# DIfferential_Current_DAC.net
KiCad netlist of a schematic drawn in Altium Designer
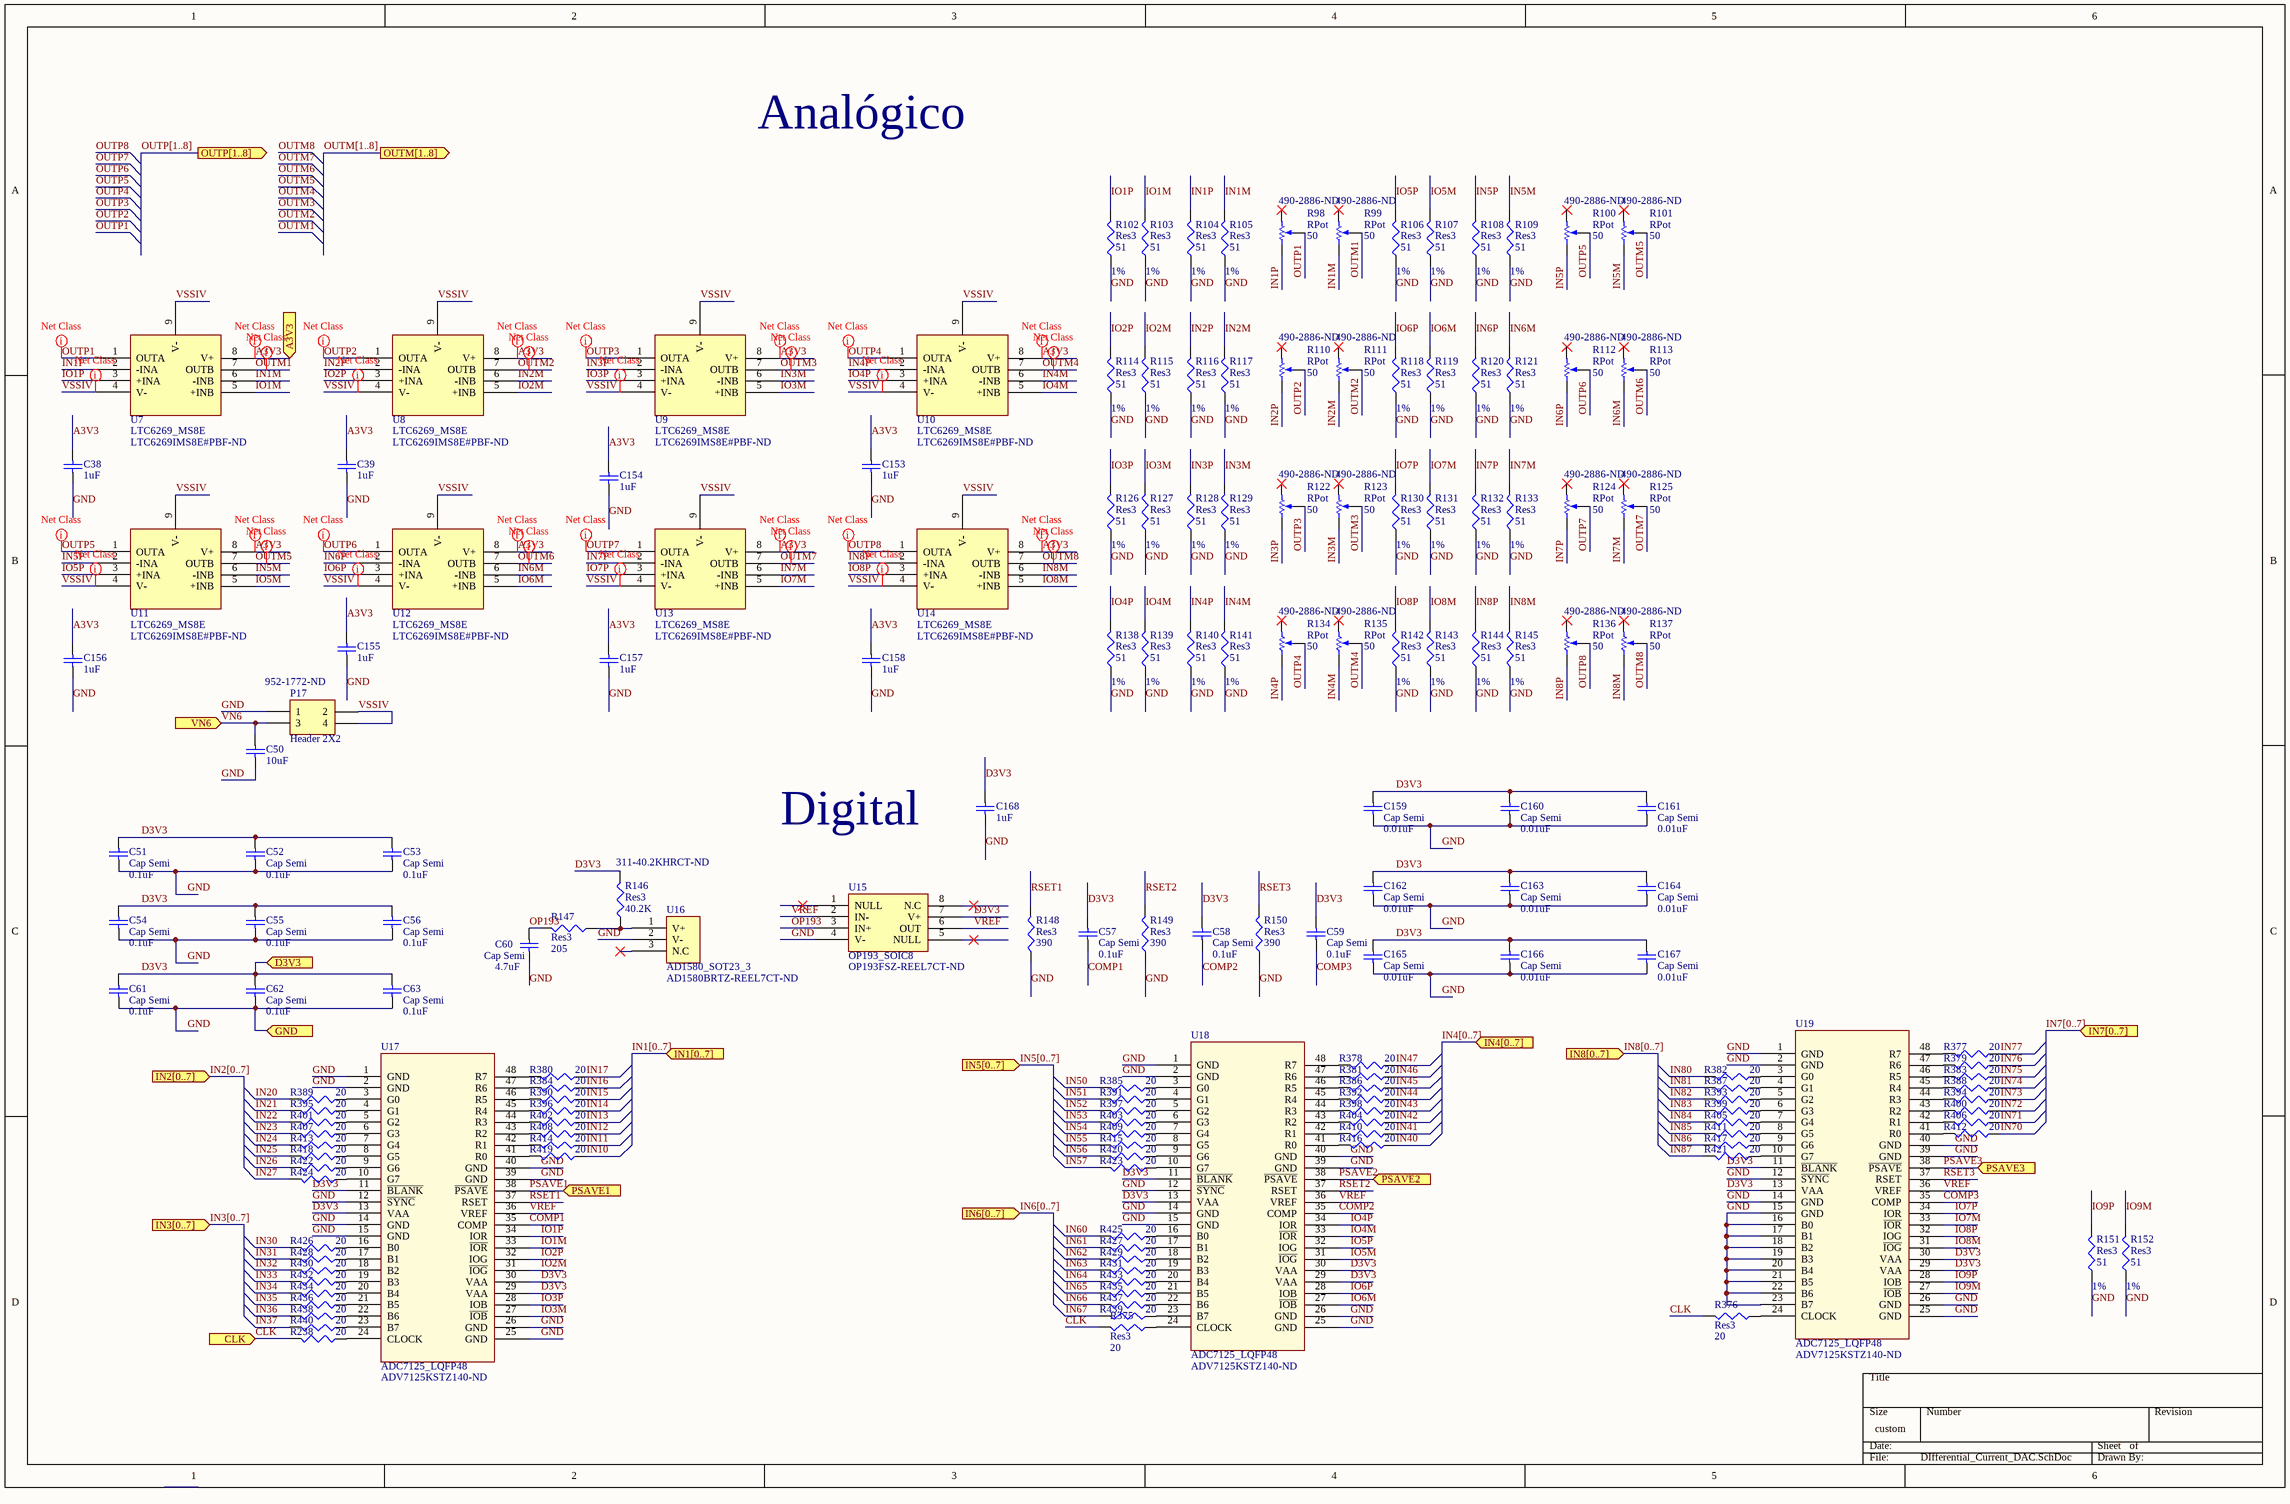
[diagram p0: DIfferential_Current_DAC.SchDoc]

(export (version "E")
  (design (tool "Eeschema 10.0.6"))
  (components
    (comp (ref "C38")
      (value "1uF")
      (footprint "J1-0603")
      (description "Capacitor")
      (fields (field (name "Comment") "Cap") (field (name "PUBLISHER") "Altium Limited"))
      (libsource (lib "Miscellaneous Devices") (part "Cap"))
    )
    (comp (ref "C39")
      (value "1uF")
      (footprint "J1-0603")
      (description "Capacitor")
      (fields (field (name "Comment") "Cap") (field (name "PUBLISHER") "Altium Limited"))
      (libsource (lib "Miscellaneous Devices") (part "Cap"))
    )
    (comp (ref "C50")
      (value "10uF")
      (footprint "RES_0805")
      (description "Capacitor")
      (fields (field (name "Comment") "Cap") (field (name "PUBLISHER") "Altium Limited"))
      (libsource (lib "Miscellaneous Devices") (part "Cap"))
    )
    (comp (ref "C51")
      (value "Cap Semi")
      (footprint "J1-0603")
      (description "Capacitor (Semiconductor SIM Model)")
      (fields (field (name "ALTIUM_VALUE") "0.1uF") (field (name "PUBLISHER") "Altium Limited"))
      (libsource (lib "Miscellaneous Devices") (part "Cap Semi"))
    )
    (comp (ref "C52")
      (value "Cap Semi")
      (footprint "J1-0603")
      (description "Capacitor (Semiconductor SIM Model)")
      (fields (field (name "ALTIUM_VALUE") "0.1uF") (field (name "PUBLISHER") "Altium Limited"))
      (libsource (lib "Miscellaneous Devices") (part "Cap Semi"))
    )
    (comp (ref "C53")
      (value "Cap Semi")
      (footprint "J1-0603")
      (description "Capacitor (Semiconductor SIM Model)")
      (fields (field (name "ALTIUM_VALUE") "0.1uF") (field (name "PUBLISHER") "Altium Limited"))
      (libsource (lib "Miscellaneous Devices") (part "Cap Semi"))
    )
    (comp (ref "C54")
      (value "Cap Semi")
      (footprint "J1-0603")
      (description "Capacitor (Semiconductor SIM Model)")
      (fields (field (name "ALTIUM_VALUE") "0.1uF") (field (name "PUBLISHER") "Altium Limited"))
      (libsource (lib "Miscellaneous Devices") (part "Cap Semi"))
    )
    (comp (ref "C55")
      (value "Cap Semi")
      (footprint "J1-0603")
      (description "Capacitor (Semiconductor SIM Model)")
      (fields (field (name "ALTIUM_VALUE") "0.1uF") (field (name "PUBLISHER") "Altium Limited"))
      (libsource (lib "Miscellaneous Devices") (part "Cap Semi"))
    )
    (comp (ref "C56")
      (value "Cap Semi")
      (footprint "J1-0603")
      (description "Capacitor (Semiconductor SIM Model)")
      (fields (field (name "ALTIUM_VALUE") "0.1uF") (field (name "PUBLISHER") "Altium Limited"))
      (libsource (lib "Miscellaneous Devices") (part "Cap Semi"))
    )
    (comp (ref "C57")
      (value "Cap Semi")
      (footprint "J1-0603")
      (description "Capacitor (Semiconductor SIM Model)")
      (fields (field (name "ALTIUM_VALUE") "0.1uF") (field (name "PUBLISHER") "Altium Limited"))
      (libsource (lib "Miscellaneous Devices") (part "Cap Semi"))
    )
    (comp (ref "C58")
      (value "Cap Semi")
      (footprint "J1-0603")
      (description "Capacitor (Semiconductor SIM Model)")
      (fields (field (name "ALTIUM_VALUE") "0.1uF") (field (name "PUBLISHER") "Altium Limited"))
      (libsource (lib "Miscellaneous Devices") (part "Cap Semi"))
    )
    (comp (ref "C59")
      (value "Cap Semi")
      (footprint "J1-0603")
      (description "Capacitor (Semiconductor SIM Model)")
      (fields (field (name "ALTIUM_VALUE") "0.1uF") (field (name "PUBLISHER") "Altium Limited"))
      (libsource (lib "Miscellaneous Devices") (part "Cap Semi"))
    )
    (comp (ref "C60")
      (value "Cap Semi")
      (footprint "J1-0603")
      (description "Capacitor (Semiconductor SIM Model)")
      (fields (field (name "ALTIUM_VALUE") "4.7uF") (field (name "PUBLISHER") "Altium Limited"))
      (libsource (lib "Miscellaneous Devices") (part "Cap Semi"))
    )
    (comp (ref "C61")
      (value "Cap Semi")
      (footprint "J1-0603")
      (description "Capacitor (Semiconductor SIM Model)")
      (fields (field (name "ALTIUM_VALUE") "0.1uF") (field (name "PUBLISHER") "Altium Limited"))
      (libsource (lib "Miscellaneous Devices") (part "Cap Semi"))
    )
    (comp (ref "C62")
      (value "Cap Semi")
      (footprint "J1-0603")
      (description "Capacitor (Semiconductor SIM Model)")
      (fields (field (name "ALTIUM_VALUE") "0.1uF") (field (name "PUBLISHER") "Altium Limited"))
      (libsource (lib "Miscellaneous Devices") (part "Cap Semi"))
    )
    (comp (ref "C63")
      (value "Cap Semi")
      (footprint "J1-0603")
      (description "Capacitor (Semiconductor SIM Model)")
      (fields (field (name "ALTIUM_VALUE") "0.1uF") (field (name "PUBLISHER") "Altium Limited"))
      (libsource (lib "Miscellaneous Devices") (part "Cap Semi"))
    )
    (comp (ref "C153")
      (value "1uF")
      (footprint "J1-0603")
      (description "Capacitor")
      (fields (field (name "Comment") "Cap") (field (name "PUBLISHER") "Altium Limited"))
      (libsource (lib "Miscellaneous Devices") (part "Cap"))
    )
    (comp (ref "C154")
      (value "1uF")
      (footprint "J1-0603")
      (description "Capacitor")
      (fields (field (name "Comment") "Cap") (field (name "PUBLISHER") "Altium Limited"))
      (libsource (lib "Miscellaneous Devices") (part "Cap"))
    )
    (comp (ref "C155")
      (value "1uF")
      (footprint "J1-0603")
      (description "Capacitor")
      (fields (field (name "Comment") "Cap") (field (name "PUBLISHER") "Altium Limited"))
      (libsource (lib "Miscellaneous Devices") (part "Cap"))
    )
    (comp (ref "C156")
      (value "1uF")
      (footprint "J1-0603")
      (description "Capacitor")
      (fields (field (name "Comment") "Cap") (field (name "PUBLISHER") "Altium Limited"))
      (libsource (lib "Miscellaneous Devices") (part "Cap"))
    )
    (comp (ref "C157")
      (value "1uF")
      (footprint "J1-0603")
      (description "Capacitor")
      (fields (field (name "Comment") "Cap") (field (name "PUBLISHER") "Altium Limited"))
      (libsource (lib "Miscellaneous Devices") (part "Cap"))
    )
    (comp (ref "C158")
      (value "1uF")
      (footprint "J1-0603")
      (description "Capacitor")
      (fields (field (name "Comment") "Cap") (field (name "PUBLISHER") "Altium Limited"))
      (libsource (lib "Miscellaneous Devices") (part "Cap"))
    )
    (comp (ref "C159")
      (value "Cap Semi")
      (footprint "J1-0603")
      (description "Capacitor (Semiconductor SIM Model)")
      (fields (field (name "ALTIUM_VALUE") "0.01uF") (field (name "PUBLISHER") "Altium Limited"))
      (libsource (lib "Miscellaneous Devices") (part "Cap Semi"))
    )
    (comp (ref "C160")
      (value "Cap Semi")
      (footprint "J1-0603")
      (description "Capacitor (Semiconductor SIM Model)")
      (fields (field (name "ALTIUM_VALUE") "0.01uF") (field (name "PUBLISHER") "Altium Limited"))
      (libsource (lib "Miscellaneous Devices") (part "Cap Semi"))
    )
    (comp (ref "C161")
      (value "Cap Semi")
      (footprint "J1-0603")
      (description "Capacitor (Semiconductor SIM Model)")
      (fields (field (name "ALTIUM_VALUE") "0.01uF") (field (name "PUBLISHER") "Altium Limited"))
      (libsource (lib "Miscellaneous Devices") (part "Cap Semi"))
    )
    (comp (ref "C162")
      (value "Cap Semi")
      (footprint "J1-0603")
      (description "Capacitor (Semiconductor SIM Model)")
      (fields (field (name "ALTIUM_VALUE") "0.01uF") (field (name "PUBLISHER") "Altium Limited"))
      (libsource (lib "Miscellaneous Devices") (part "Cap Semi"))
    )
    (comp (ref "C163")
      (value "Cap Semi")
      (footprint "J1-0603")
      (description "Capacitor (Semiconductor SIM Model)")
      (fields (field (name "ALTIUM_VALUE") "0.01uF") (field (name "PUBLISHER") "Altium Limited"))
      (libsource (lib "Miscellaneous Devices") (part "Cap Semi"))
    )
    (comp (ref "C164")
      (value "Cap Semi")
      (footprint "J1-0603")
      (description "Capacitor (Semiconductor SIM Model)")
      (fields (field (name "ALTIUM_VALUE") "0.01uF") (field (name "PUBLISHER") "Altium Limited"))
      (libsource (lib "Miscellaneous Devices") (part "Cap Semi"))
    )
    (comp (ref "C165")
      (value "Cap Semi")
      (footprint "J1-0603")
      (description "Capacitor (Semiconductor SIM Model)")
      (fields (field (name "ALTIUM_VALUE") "0.01uF") (field (name "PUBLISHER") "Altium Limited"))
      (libsource (lib "Miscellaneous Devices") (part "Cap Semi"))
    )
    (comp (ref "C166")
      (value "Cap Semi")
      (footprint "J1-0603")
      (description "Capacitor (Semiconductor SIM Model)")
      (fields (field (name "ALTIUM_VALUE") "0.01uF") (field (name "PUBLISHER") "Altium Limited"))
      (libsource (lib "Miscellaneous Devices") (part "Cap Semi"))
    )
    (comp (ref "C167")
      (value "Cap Semi")
      (footprint "J1-0603")
      (description "Capacitor (Semiconductor SIM Model)")
      (fields (field (name "ALTIUM_VALUE") "0.01uF") (field (name "PUBLISHER") "Altium Limited"))
      (libsource (lib "Miscellaneous Devices") (part "Cap Semi"))
    )
    (comp (ref "C168")
      (value "1uF")
      (footprint "J1-0603")
      (description "Capacitor")
      (fields (field (name "Comment") "Cap") (field (name "PUBLISHER") "Altium Limited"))
      (libsource (lib "Miscellaneous Devices") (part "Cap"))
    )
    (comp (ref "P17")
      (value "Header 2X2")
      (footprint "HDR2X2")
      (description "Header, 2-Pin, Dual row")
      (fields
        (field (name "SUPPLIER PART NUMBER 1") "952-1772-ND")
        (field (name "PUBLISHER") "Altium Limited")
      )
      (libsource (lib "Miscellaneous Connectors") (part "Header 2X2"))
    )
    (comp (ref "R98")
      (value "RPot")
      (footprint "VR5")
      (description "Potentiometer")
      (fields
        (field (name "ALTIUM_VALUE") "50")
        (field (name "SUPPLIER PART NUMBER 1") "490-2886-ND")
        (field (name "PUBLISHER") "Altium Limited")
      )
      (libsource (lib "Lib1") (part "RPot"))
    )
    (comp (ref "R99")
      (value "RPot")
      (footprint "VR5")
      (description "Potentiometer")
      (fields
        (field (name "ALTIUM_VALUE") "50")
        (field (name "SUPPLIER PART NUMBER 1") "490-2886-ND")
        (field (name "PUBLISHER") "Altium Limited")
      )
      (libsource (lib "Lib1") (part "RPot"))
    )
    (comp (ref "R100")
      (value "RPot")
      (footprint "VR5")
      (description "Potentiometer")
      (fields
        (field (name "ALTIUM_VALUE") "50")
        (field (name "SUPPLIER PART NUMBER 1") "490-2886-ND")
        (field (name "PUBLISHER") "Altium Limited")
      )
      (libsource (lib "Lib1") (part "RPot"))
    )
    (comp (ref "R101")
      (value "RPot")
      (footprint "VR5")
      (description "Potentiometer")
      (fields
        (field (name "ALTIUM_VALUE") "50")
        (field (name "SUPPLIER PART NUMBER 1") "490-2886-ND")
        (field (name "PUBLISHER") "Altium Limited")
      )
      (libsource (lib "Lib1") (part "RPot"))
    )
    (comp (ref "R102")
      (value "Res3")
      (footprint "J1-0603")
      (description "Resistor")
      (fields
        (field (name "ALTIUM_VALUE") "51")
        (field (name "TOLERANCE") "1%")
        (field (name "PUBLISHER") "Altium Limited")
      )
      (libsource (lib "Miscellaneous Devices") (part "Res3"))
    )
    (comp (ref "R103")
      (value "Res3")
      (footprint "J1-0603")
      (description "Resistor")
      (fields
        (field (name "ALTIUM_VALUE") "51")
        (field (name "TOLERANCE") "1%")
        (field (name "PUBLISHER") "Altium Limited")
      )
      (libsource (lib "Miscellaneous Devices") (part "Res3"))
    )
    (comp (ref "R104")
      (value "Res3")
      (footprint "J1-0603")
      (description "Resistor")
      (fields
        (field (name "ALTIUM_VALUE") "51")
        (field (name "TOLERANCE") "1%")
        (field (name "PUBLISHER") "Altium Limited")
      )
      (libsource (lib "Miscellaneous Devices") (part "Res3"))
    )
    (comp (ref "R105")
      (value "Res3")
      (footprint "J1-0603")
      (description "Resistor")
      (fields
        (field (name "ALTIUM_VALUE") "51")
        (field (name "TOLERANCE") "1%")
        (field (name "PUBLISHER") "Altium Limited")
      )
      (libsource (lib "Miscellaneous Devices") (part "Res3"))
    )
    (comp (ref "R106")
      (value "Res3")
      (footprint "J1-0603")
      (description "Resistor")
      (fields
        (field (name "ALTIUM_VALUE") "51")
        (field (name "TOLERANCE") "1%")
        (field (name "PUBLISHER") "Altium Limited")
      )
      (libsource (lib "Miscellaneous Devices") (part "Res3"))
    )
    (comp (ref "R107")
      (value "Res3")
      (footprint "J1-0603")
      (description "Resistor")
      (fields
        (field (name "ALTIUM_VALUE") "51")
        (field (name "TOLERANCE") "1%")
        (field (name "PUBLISHER") "Altium Limited")
      )
      (libsource (lib "Miscellaneous Devices") (part "Res3"))
    )
    (comp (ref "R108")
      (value "Res3")
      (footprint "J1-0603")
      (description "Resistor")
      (fields
        (field (name "ALTIUM_VALUE") "51")
        (field (name "TOLERANCE") "1%")
        (field (name "PUBLISHER") "Altium Limited")
      )
      (libsource (lib "Miscellaneous Devices") (part "Res3"))
    )
    (comp (ref "R109")
      (value "Res3")
      (footprint "J1-0603")
      (description "Resistor")
      (fields
        (field (name "ALTIUM_VALUE") "51")
        (field (name "TOLERANCE") "1%")
        (field (name "PUBLISHER") "Altium Limited")
      )
      (libsource (lib "Miscellaneous Devices") (part "Res3"))
    )
    (comp (ref "R110")
      (value "RPot")
      (footprint "VR5")
      (description "Potentiometer")
      (fields
        (field (name "ALTIUM_VALUE") "50")
        (field (name "SUPPLIER PART NUMBER 1") "490-2886-ND")
        (field (name "PUBLISHER") "Altium Limited")
      )
      (libsource (lib "Lib1") (part "RPot"))
    )
    (comp (ref "R111")
      (value "RPot")
      (footprint "VR5")
      (description "Potentiometer")
      (fields
        (field (name "ALTIUM_VALUE") "50")
        (field (name "SUPPLIER PART NUMBER 1") "490-2886-ND")
        (field (name "PUBLISHER") "Altium Limited")
      )
      (libsource (lib "Lib1") (part "RPot"))
    )
    (comp (ref "R112")
      (value "RPot")
      (footprint "VR5")
      (description "Potentiometer")
      (fields
        (field (name "ALTIUM_VALUE") "50")
        (field (name "SUPPLIER PART NUMBER 1") "490-2886-ND")
        (field (name "PUBLISHER") "Altium Limited")
      )
      (libsource (lib "Lib1") (part "RPot"))
    )
    (comp (ref "R113")
      (value "RPot")
      (footprint "VR5")
      (description "Potentiometer")
      (fields
        (field (name "ALTIUM_VALUE") "50")
        (field (name "SUPPLIER PART NUMBER 1") "490-2886-ND")
        (field (name "PUBLISHER") "Altium Limited")
      )
      (libsource (lib "Lib1") (part "RPot"))
    )
    (comp (ref "R114")
      (value "Res3")
      (footprint "J1-0603")
      (description "Resistor")
      (fields
        (field (name "ALTIUM_VALUE") "51")
        (field (name "TOLERANCE") "1%")
        (field (name "PUBLISHER") "Altium Limited")
      )
      (libsource (lib "Miscellaneous Devices") (part "Res3"))
    )
    (comp (ref "R115")
      (value "Res3")
      (footprint "J1-0603")
      (description "Resistor")
      (fields
        (field (name "ALTIUM_VALUE") "51")
        (field (name "TOLERANCE") "1%")
        (field (name "PUBLISHER") "Altium Limited")
      )
      (libsource (lib "Miscellaneous Devices") (part "Res3"))
    )
    (comp (ref "R116")
      (value "Res3")
      (footprint "J1-0603")
      (description "Resistor")
      (fields
        (field (name "ALTIUM_VALUE") "51")
        (field (name "TOLERANCE") "1%")
        (field (name "PUBLISHER") "Altium Limited")
      )
      (libsource (lib "Miscellaneous Devices") (part "Res3"))
    )
    (comp (ref "R117")
      (value "Res3")
      (footprint "J1-0603")
      (description "Resistor")
      (fields
        (field (name "ALTIUM_VALUE") "51")
        (field (name "TOLERANCE") "1%")
        (field (name "PUBLISHER") "Altium Limited")
      )
      (libsource (lib "Miscellaneous Devices") (part "Res3"))
    )
    (comp (ref "R118")
      (value "Res3")
      (footprint "J1-0603")
      (description "Resistor")
      (fields
        (field (name "ALTIUM_VALUE") "51")
        (field (name "TOLERANCE") "1%")
        (field (name "PUBLISHER") "Altium Limited")
      )
      (libsource (lib "Miscellaneous Devices") (part "Res3"))
    )
    (comp (ref "R119")
      (value "Res3")
      (footprint "J1-0603")
      (description "Resistor")
      (fields
        (field (name "ALTIUM_VALUE") "51")
        (field (name "TOLERANCE") "1%")
        (field (name "PUBLISHER") "Altium Limited")
      )
      (libsource (lib "Miscellaneous Devices") (part "Res3"))
    )
    (comp (ref "R120")
      (value "Res3")
      (footprint "J1-0603")
      (description "Resistor")
      (fields
        (field (name "ALTIUM_VALUE") "51")
        (field (name "TOLERANCE") "1%")
        (field (name "PUBLISHER") "Altium Limited")
      )
      (libsource (lib "Miscellaneous Devices") (part "Res3"))
    )
    (comp (ref "R121")
      (value "Res3")
      (footprint "J1-0603")
      (description "Resistor")
      (fields
        (field (name "ALTIUM_VALUE") "51")
        (field (name "TOLERANCE") "1%")
        (field (name "PUBLISHER") "Altium Limited")
      )
      (libsource (lib "Miscellaneous Devices") (part "Res3"))
    )
    (comp (ref "R122")
      (value "RPot")
      (footprint "VR5")
      (description "Potentiometer")
      (fields
        (field (name "ALTIUM_VALUE") "50")
        (field (name "SUPPLIER PART NUMBER 1") "490-2886-ND")
        (field (name "PUBLISHER") "Altium Limited")
      )
      (libsource (lib "Lib1") (part "RPot"))
    )
    (comp (ref "R123")
      (value "RPot")
      (footprint "VR5")
      (description "Potentiometer")
      (fields
        (field (name "ALTIUM_VALUE") "50")
        (field (name "SUPPLIER PART NUMBER 1") "490-2886-ND")
        (field (name "PUBLISHER") "Altium Limited")
      )
      (libsource (lib "Lib1") (part "RPot"))
    )
    (comp (ref "R124")
      (value "RPot")
      (footprint "VR5")
      (description "Potentiometer")
      (fields
        (field (name "ALTIUM_VALUE") "50")
        (field (name "SUPPLIER PART NUMBER 1") "490-2886-ND")
        (field (name "PUBLISHER") "Altium Limited")
      )
      (libsource (lib "Lib1") (part "RPot"))
    )
    (comp (ref "R125")
      (value "RPot")
      (footprint "VR5")
      (description "Potentiometer")
      (fields
        (field (name "ALTIUM_VALUE") "50")
        (field (name "SUPPLIER PART NUMBER 1") "490-2886-ND")
        (field (name "PUBLISHER") "Altium Limited")
      )
      (libsource (lib "Lib1") (part "RPot"))
    )
    (comp (ref "R126")
      (value "Res3")
      (footprint "J1-0603")
      (description "Resistor")
      (fields
        (field (name "ALTIUM_VALUE") "51")
        (field (name "TOLERANCE") "1%")
        (field (name "PUBLISHER") "Altium Limited")
      )
      (libsource (lib "Miscellaneous Devices") (part "Res3"))
    )
    (comp (ref "R127")
      (value "Res3")
      (footprint "J1-0603")
      (description "Resistor")
      (fields
        (field (name "ALTIUM_VALUE") "51")
        (field (name "TOLERANCE") "1%")
        (field (name "PUBLISHER") "Altium Limited")
      )
      (libsource (lib "Miscellaneous Devices") (part "Res3"))
    )
    (comp (ref "R128")
      (value "Res3")
      (footprint "J1-0603")
      (description "Resistor")
      (fields
        (field (name "ALTIUM_VALUE") "51")
        (field (name "TOLERANCE") "1%")
        (field (name "PUBLISHER") "Altium Limited")
      )
      (libsource (lib "Miscellaneous Devices") (part "Res3"))
    )
    (comp (ref "R129")
      (value "Res3")
      (footprint "J1-0603")
      (description "Resistor")
      (fields
        (field (name "ALTIUM_VALUE") "51")
        (field (name "TOLERANCE") "1%")
        (field (name "PUBLISHER") "Altium Limited")
      )
      (libsource (lib "Miscellaneous Devices") (part "Res3"))
    )
    (comp (ref "R130")
      (value "Res3")
      (footprint "J1-0603")
      (description "Resistor")
      (fields
        (field (name "ALTIUM_VALUE") "51")
        (field (name "TOLERANCE") "1%")
        (field (name "PUBLISHER") "Altium Limited")
      )
      (libsource (lib "Miscellaneous Devices") (part "Res3"))
    )
    (comp (ref "R131")
      (value "Res3")
      (footprint "J1-0603")
      (description "Resistor")
      (fields
        (field (name "ALTIUM_VALUE") "51")
        (field (name "TOLERANCE") "1%")
        (field (name "PUBLISHER") "Altium Limited")
      )
      (libsource (lib "Miscellaneous Devices") (part "Res3"))
    )
    (comp (ref "R132")
      (value "Res3")
      (footprint "J1-0603")
      (description "Resistor")
      (fields
        (field (name "ALTIUM_VALUE") "51")
        (field (name "TOLERANCE") "1%")
        (field (name "PUBLISHER") "Altium Limited")
      )
      (libsource (lib "Miscellaneous Devices") (part "Res3"))
    )
    (comp (ref "R133")
      (value "Res3")
      (footprint "J1-0603")
      (description "Resistor")
      (fields
        (field (name "ALTIUM_VALUE") "51")
        (field (name "TOLERANCE") "1%")
        (field (name "PUBLISHER") "Altium Limited")
      )
      (libsource (lib "Miscellaneous Devices") (part "Res3"))
    )
    (comp (ref "R134")
      (value "RPot")
      (footprint "VR5")
      (description "Potentiometer")
      (fields
        (field (name "ALTIUM_VALUE") "50")
        (field (name "SUPPLIER PART NUMBER 1") "490-2886-ND")
        (field (name "PUBLISHER") "Altium Limited")
      )
      (libsource (lib "Lib1") (part "RPot"))
    )
    (comp (ref "R135")
      (value "RPot")
      (footprint "VR5")
      (description "Potentiometer")
      (fields
        (field (name "ALTIUM_VALUE") "50")
        (field (name "SUPPLIER PART NUMBER 1") "490-2886-ND")
        (field (name "PUBLISHER") "Altium Limited")
      )
      (libsource (lib "Lib1") (part "RPot"))
    )
    (comp (ref "R136")
      (value "RPot")
      (footprint "VR5")
      (description "Potentiometer")
      (fields
        (field (name "ALTIUM_VALUE") "50")
        (field (name "SUPPLIER PART NUMBER 1") "490-2886-ND")
        (field (name "PUBLISHER") "Altium Limited")
      )
      (libsource (lib "Lib1") (part "RPot"))
    )
    (comp (ref "R137")
      (value "RPot")
      (footprint "VR5")
      (description "Potentiometer")
      (fields
        (field (name "ALTIUM_VALUE") "50")
        (field (name "SUPPLIER PART NUMBER 1") "490-2886-ND")
        (field (name "PUBLISHER") "Altium Limited")
      )
      (libsource (lib "Lib1") (part "RPot"))
    )
    (comp (ref "R138")
      (value "Res3")
      (footprint "J1-0603")
      (description "Resistor")
      (fields
        (field (name "ALTIUM_VALUE") "51")
        (field (name "TOLERANCE") "1%")
        (field (name "PUBLISHER") "Altium Limited")
      )
      (libsource (lib "Miscellaneous Devices") (part "Res3"))
    )
    (comp (ref "R139")
      (value "Res3")
      (footprint "J1-0603")
      (description "Resistor")
      (fields
        (field (name "ALTIUM_VALUE") "51")
        (field (name "TOLERANCE") "1%")
        (field (name "PUBLISHER") "Altium Limited")
      )
      (libsource (lib "Miscellaneous Devices") (part "Res3"))
    )
    (comp (ref "R140")
      (value "Res3")
      (footprint "J1-0603")
      (description "Resistor")
      (fields
        (field (name "ALTIUM_VALUE") "51")
        (field (name "TOLERANCE") "1%")
        (field (name "PUBLISHER") "Altium Limited")
      )
      (libsource (lib "Miscellaneous Devices") (part "Res3"))
    )
    (comp (ref "R141")
      (value "Res3")
      (footprint "J1-0603")
      (description "Resistor")
      (fields
        (field (name "ALTIUM_VALUE") "51")
        (field (name "TOLERANCE") "1%")
        (field (name "PUBLISHER") "Altium Limited")
      )
      (libsource (lib "Miscellaneous Devices") (part "Res3"))
    )
    (comp (ref "R142")
      (value "Res3")
      (footprint "J1-0603")
      (description "Resistor")
      (fields
        (field (name "ALTIUM_VALUE") "51")
        (field (name "TOLERANCE") "1%")
        (field (name "PUBLISHER") "Altium Limited")
      )
      (libsource (lib "Miscellaneous Devices") (part "Res3"))
    )
    (comp (ref "R143")
      (value "Res3")
      (footprint "J1-0603")
      (description "Resistor")
      (fields
        (field (name "ALTIUM_VALUE") "51")
        (field (name "TOLERANCE") "1%")
        (field (name "PUBLISHER") "Altium Limited")
      )
      (libsource (lib "Miscellaneous Devices") (part "Res3"))
    )
    (comp (ref "R144")
      (value "Res3")
      (footprint "J1-0603")
      (description "Resistor")
      (fields
        (field (name "ALTIUM_VALUE") "51")
        (field (name "TOLERANCE") "1%")
        (field (name "PUBLISHER") "Altium Limited")
      )
      (libsource (lib "Miscellaneous Devices") (part "Res3"))
    )
    (comp (ref "R145")
      (value "Res3")
      (footprint "J1-0603")
      (description "Resistor")
      (fields
        (field (name "ALTIUM_VALUE") "51")
        (field (name "TOLERANCE") "1%")
        (field (name "PUBLISHER") "Altium Limited")
      )
      (libsource (lib "Miscellaneous Devices") (part "Res3"))
    )
    (comp (ref "R146")
      (value "Res3")
      (footprint "J1-0603")
      (description "Resistor")
      (fields
        (field (name "ALTIUM_VALUE") "40.2K")
        (field (name "SUPPLIER PART NUMBER 1") "311-40.2KHRCT-ND")
        (field (name "PUBLISHER") "Altium Limited")
      )
      (libsource (lib "Miscellaneous Devices") (part "Res3"))
    )
    (comp (ref "R147")
      (value "Res3")
      (footprint "J1-0603")
      (description "Resistor")
      (fields (field (name "ALTIUM_VALUE") "205") (field (name "PUBLISHER") "Altium Limited"))
      (libsource (lib "Miscellaneous Devices") (part "Res3"))
    )
    (comp (ref "R148")
      (value "Res3")
      (footprint "J1-0603")
      (description "Resistor")
      (fields (field (name "ALTIUM_VALUE") "390") (field (name "PUBLISHER") "Altium Limited"))
      (libsource (lib "Miscellaneous Devices") (part "Res3"))
    )
    (comp (ref "R149")
      (value "Res3")
      (footprint "J1-0603")
      (description "Resistor")
      (fields (field (name "ALTIUM_VALUE") "390") (field (name "PUBLISHER") "Altium Limited"))
      (libsource (lib "Miscellaneous Devices") (part "Res3"))
    )
    (comp (ref "R150")
      (value "Res3")
      (footprint "J1-0603")
      (description "Resistor")
      (fields (field (name "ALTIUM_VALUE") "390") (field (name "PUBLISHER") "Altium Limited"))
      (libsource (lib "Miscellaneous Devices") (part "Res3"))
    )
    (comp (ref "R151")
      (value "Res3")
      (footprint "J1-0603")
      (description "Resistor")
      (fields
        (field (name "ALTIUM_VALUE") "51")
        (field (name "TOLERANCE") "1%")
        (field (name "PUBLISHER") "Altium Limited")
      )
      (libsource (lib "Miscellaneous Devices") (part "Res3"))
    )
    (comp (ref "R152")
      (value "Res3")
      (footprint "J1-0603")
      (description "Resistor")
      (fields
        (field (name "ALTIUM_VALUE") "51")
        (field (name "TOLERANCE") "1%")
        (field (name "PUBLISHER") "Altium Limited")
      )
      (libsource (lib "Miscellaneous Devices") (part "Res3"))
    )
    (comp (ref "R238")
      (value "20")
      (footprint "R0402")
      (description "Resistor")
      (fields (field (name "Comment") "Res3") (field (name "PUBLISHER") "Altium Limited"))
      (libsource (lib "Miscellaneous Devices") (part "Res3"))
    )
    (comp (ref "R375")
      (value "Res3")
      (footprint "R0402")
      (description "Resistor")
      (fields (field (name "ALTIUM_VALUE") "20") (field (name "PUBLISHER") "Altium Limited"))
      (libsource (lib "Miscellaneous Devices") (part "Res3"))
    )
    (comp (ref "R376")
      (value "Res3")
      (footprint "R0402")
      (description "Resistor")
      (fields (field (name "ALTIUM_VALUE") "20") (field (name "PUBLISHER") "Altium Limited"))
      (libsource (lib "Miscellaneous Devices") (part "Res3"))
    )
    (comp (ref "R377")
      (value "20")
      (footprint "R0402")
      (description "Resistor")
      (fields (field (name "Comment") "Res3") (field (name "PUBLISHER") "Altium Limited"))
      (libsource (lib "Miscellaneous Devices") (part "Res3"))
    )
    (comp (ref "R378")
      (value "20")
      (footprint "R0402")
      (description "Resistor")
      (fields (field (name "Comment") "Res3") (field (name "PUBLISHER") "Altium Limited"))
      (libsource (lib "Miscellaneous Devices") (part "Res3"))
    )
    (comp (ref "R379")
      (value "20")
      (footprint "R0402")
      (description "Resistor")
      (fields (field (name "Comment") "Res3") (field (name "PUBLISHER") "Altium Limited"))
      (libsource (lib "Miscellaneous Devices") (part "Res3"))
    )
    (comp (ref "R380")
      (value "20")
      (footprint "R0402")
      (description "Resistor")
      (fields (field (name "Comment") "Res3") (field (name "PUBLISHER") "Altium Limited"))
      (libsource (lib "Miscellaneous Devices") (part "Res3"))
    )
    (comp (ref "R381")
      (value "20")
      (footprint "R0402")
      (description "Resistor")
      (fields (field (name "Comment") "Res3") (field (name "PUBLISHER") "Altium Limited"))
      (libsource (lib "Miscellaneous Devices") (part "Res3"))
    )
    (comp (ref "R382")
      (value "20")
      (footprint "R0402")
      (description "Resistor")
      (fields (field (name "Comment") "Res3") (field (name "PUBLISHER") "Altium Limited"))
      (libsource (lib "Miscellaneous Devices") (part "Res3"))
    )
    (comp (ref "R383")
      (value "20")
      (footprint "R0402")
      (description "Resistor")
      (fields (field (name "Comment") "Res3") (field (name "PUBLISHER") "Altium Limited"))
      (libsource (lib "Miscellaneous Devices") (part "Res3"))
    )
    (comp (ref "R384")
      (value "20")
      (footprint "R0402")
      (description "Resistor")
      (fields (field (name "Comment") "Res3") (field (name "PUBLISHER") "Altium Limited"))
      (libsource (lib "Miscellaneous Devices") (part "Res3"))
    )
    (comp (ref "R385")
      (value "20")
      (footprint "R0402")
      (description "Resistor")
      (fields (field (name "Comment") "Res3") (field (name "PUBLISHER") "Altium Limited"))
      (libsource (lib "Miscellaneous Devices") (part "Res3"))
    )
    (comp (ref "R386")
      (value "20")
      (footprint "R0402")
      (description "Resistor")
      (fields (field (name "Comment") "Res3") (field (name "PUBLISHER") "Altium Limited"))
      (libsource (lib "Miscellaneous Devices") (part "Res3"))
    )
    (comp (ref "R387")
      (value "20")
      (footprint "R0402")
      (description "Resistor")
      (fields (field (name "Comment") "Res3") (field (name "PUBLISHER") "Altium Limited"))
      (libsource (lib "Miscellaneous Devices") (part "Res3"))
    )
    (comp (ref "R388")
      (value "20")
      (footprint "R0402")
      (description "Resistor")
      (fields (field (name "Comment") "Res3") (field (name "PUBLISHER") "Altium Limited"))
      (libsource (lib "Miscellaneous Devices") (part "Res3"))
    )
    (comp (ref "R389")
      (value "20")
      (footprint "R0402")
      (description "Resistor")
      (fields (field (name "Comment") "Res3") (field (name "PUBLISHER") "Altium Limited"))
      (libsource (lib "Miscellaneous Devices") (part "Res3"))
    )
    (comp (ref "R390")
      (value "20")
      (footprint "R0402")
      (description "Resistor")
      (fields (field (name "Comment") "Res3") (field (name "PUBLISHER") "Altium Limited"))
      (libsource (lib "Miscellaneous Devices") (part "Res3"))
    )
    (comp (ref "R391")
      (value "20")
      (footprint "R0402")
      (description "Resistor")
      (fields (field (name "Comment") "Res3") (field (name "PUBLISHER") "Altium Limited"))
      (libsource (lib "Miscellaneous Devices") (part "Res3"))
    )
    (comp (ref "R392")
      (value "20")
      (footprint "R0402")
      (description "Resistor")
      (fields (field (name "Comment") "Res3") (field (name "PUBLISHER") "Altium Limited"))
      (libsource (lib "Miscellaneous Devices") (part "Res3"))
    )
    (comp (ref "R393")
      (value "20")
      (footprint "R0402")
      (description "Resistor")
      (fields (field (name "Comment") "Res3") (field (name "PUBLISHER") "Altium Limited"))
      (libsource (lib "Miscellaneous Devices") (part "Res3"))
    )
    (comp (ref "R394")
      (value "20")
      (footprint "R0402")
      (description "Resistor")
      (fields (field (name "Comment") "Res3") (field (name "PUBLISHER") "Altium Limited"))
      (libsource (lib "Miscellaneous Devices") (part "Res3"))
    )
    (comp (ref "R395")
      (value "20")
      (footprint "R0402")
      (description "Resistor")
      (fields (field (name "Comment") "Res3") (field (name "PUBLISHER") "Altium Limited"))
      (libsource (lib "Miscellaneous Devices") (part "Res3"))
    )
    (comp (ref "R396")
      (value "20")
      (footprint "R0402")
      (description "Resistor")
      (fields (field (name "Comment") "Res3") (field (name "PUBLISHER") "Altium Limited"))
      (libsource (lib "Miscellaneous Devices") (part "Res3"))
    )
    (comp (ref "R397")
      (value "20")
      (footprint "R0402")
      (description "Resistor")
      (fields (field (name "Comment") "Res3") (field (name "PUBLISHER") "Altium Limited"))
      (libsource (lib "Miscellaneous Devices") (part "Res3"))
    )
    (comp (ref "R398")
      (value "20")
      (footprint "R0402")
      (description "Resistor")
      (fields (field (name "Comment") "Res3") (field (name "PUBLISHER") "Altium Limited"))
      (libsource (lib "Miscellaneous Devices") (part "Res3"))
    )
    (comp (ref "R399")
      (value "20")
      (footprint "R0402")
      (description "Resistor")
      (fields (field (name "Comment") "Res3") (field (name "PUBLISHER") "Altium Limited"))
      (libsource (lib "Miscellaneous Devices") (part "Res3"))
    )
    (comp (ref "R400")
      (value "20")
      (footprint "R0402")
      (description "Resistor")
      (fields (field (name "Comment") "Res3") (field (name "PUBLISHER") "Altium Limited"))
      (libsource (lib "Miscellaneous Devices") (part "Res3"))
    )
    (comp (ref "R401")
      (value "20")
      (footprint "R0402")
      (description "Resistor")
      (fields (field (name "Comment") "Res3") (field (name "PUBLISHER") "Altium Limited"))
      (libsource (lib "Miscellaneous Devices") (part "Res3"))
    )
    (comp (ref "R402")
      (value "20")
      (footprint "R0402")
      (description "Resistor")
      (fields (field (name "Comment") "Res3") (field (name "PUBLISHER") "Altium Limited"))
      (libsource (lib "Miscellaneous Devices") (part "Res3"))
    )
    (comp (ref "R403")
      (value "20")
      (footprint "R0402")
      (description "Resistor")
      (fields (field (name "Comment") "Res3") (field (name "PUBLISHER") "Altium Limited"))
      (libsource (lib "Miscellaneous Devices") (part "Res3"))
    )
    (comp (ref "R404")
      (value "20")
      (footprint "R0402")
      (description "Resistor")
      (fields (field (name "Comment") "Res3") (field (name "PUBLISHER") "Altium Limited"))
      (libsource (lib "Miscellaneous Devices") (part "Res3"))
    )
    (comp (ref "R405")
      (value "20")
      (footprint "R0402")
      (description "Resistor")
      (fields (field (name "Comment") "Res3") (field (name "PUBLISHER") "Altium Limited"))
      (libsource (lib "Miscellaneous Devices") (part "Res3"))
    )
    (comp (ref "R406")
      (value "20")
      (footprint "R0402")
      (description "Resistor")
      (fields (field (name "Comment") "Res3") (field (name "PUBLISHER") "Altium Limited"))
      (libsource (lib "Miscellaneous Devices") (part "Res3"))
    )
    (comp (ref "R407")
      (value "20")
      (footprint "R0402")
      (description "Resistor")
      (fields (field (name "Comment") "Res3") (field (name "PUBLISHER") "Altium Limited"))
      (libsource (lib "Miscellaneous Devices") (part "Res3"))
    )
    (comp (ref "R408")
      (value "20")
      (footprint "R0402")
      (description "Resistor")
      (fields (field (name "Comment") "Res3") (field (name "PUBLISHER") "Altium Limited"))
      (libsource (lib "Miscellaneous Devices") (part "Res3"))
    )
    (comp (ref "R409")
      (value "20")
      (footprint "R0402")
      (description "Resistor")
      (fields (field (name "Comment") "Res3") (field (name "PUBLISHER") "Altium Limited"))
      (libsource (lib "Miscellaneous Devices") (part "Res3"))
    )
    (comp (ref "R410")
      (value "20")
      (footprint "R0402")
      (description "Resistor")
      (fields (field (name "Comment") "Res3") (field (name "PUBLISHER") "Altium Limited"))
      (libsource (lib "Miscellaneous Devices") (part "Res3"))
    )
    (comp (ref "R411")
      (value "20")
      (footprint "R0402")
      (description "Resistor")
      (fields (field (name "Comment") "Res3") (field (name "PUBLISHER") "Altium Limited"))
      (libsource (lib "Miscellaneous Devices") (part "Res3"))
    )
    (comp (ref "R412")
      (value "20")
      (footprint "R0402")
      (description "Resistor")
      (fields (field (name "Comment") "Res3") (field (name "PUBLISHER") "Altium Limited"))
      (libsource (lib "Miscellaneous Devices") (part "Res3"))
    )
    (comp (ref "R413")
      (value "20")
      (footprint "R0402")
      (description "Resistor")
      (fields (field (name "Comment") "Res3") (field (name "PUBLISHER") "Altium Limited"))
      (libsource (lib "Miscellaneous Devices") (part "Res3"))
    )
    (comp (ref "R414")
      (value "20")
      (footprint "R0402")
      (description "Resistor")
      (fields (field (name "Comment") "Res3") (field (name "PUBLISHER") "Altium Limited"))
      (libsource (lib "Miscellaneous Devices") (part "Res3"))
    )
    (comp (ref "R415")
      (value "20")
      (footprint "R0402")
      (description "Resistor")
      (fields (field (name "Comment") "Res3") (field (name "PUBLISHER") "Altium Limited"))
      (libsource (lib "Miscellaneous Devices") (part "Res3"))
    )
    (comp (ref "R416")
      (value "20")
      (footprint "R0402")
      (description "Resistor")
      (fields (field (name "Comment") "Res3") (field (name "PUBLISHER") "Altium Limited"))
      (libsource (lib "Miscellaneous Devices") (part "Res3"))
    )
    (comp (ref "R417")
      (value "20")
      (footprint "R0402")
      (description "Resistor")
      (fields (field (name "Comment") "Res3") (field (name "PUBLISHER") "Altium Limited"))
      (libsource (lib "Miscellaneous Devices") (part "Res3"))
    )
    (comp (ref "R418")
      (value "20")
      (footprint "R0402")
      (description "Resistor")
      (fields (field (name "Comment") "Res3") (field (name "PUBLISHER") "Altium Limited"))
      (libsource (lib "Miscellaneous Devices") (part "Res3"))
    )
    (comp (ref "R419")
      (value "20")
      (footprint "R0402")
      (description "Resistor")
      (fields (field (name "Comment") "Res3") (field (name "PUBLISHER") "Altium Limited"))
      (libsource (lib "Miscellaneous Devices") (part "Res3"))
    )
    (comp (ref "R420")
      (value "20")
      (footprint "R0402")
      (description "Resistor")
      (fields (field (name "Comment") "Res3") (field (name "PUBLISHER") "Altium Limited"))
      (libsource (lib "Miscellaneous Devices") (part "Res3"))
    )
    (comp (ref "R421")
      (value "20")
      (footprint "R0402")
      (description "Resistor")
      (fields (field (name "Comment") "Res3") (field (name "PUBLISHER") "Altium Limited"))
      (libsource (lib "Miscellaneous Devices") (part "Res3"))
    )
    (comp (ref "R422")
      (value "20")
      (footprint "R0402")
      (description "Resistor")
      (fields (field (name "Comment") "Res3") (field (name "PUBLISHER") "Altium Limited"))
      (libsource (lib "Miscellaneous Devices") (part "Res3"))
    )
    (comp (ref "R423")
      (value "20")
      (footprint "R0402")
      (description "Resistor")
      (fields (field (name "Comment") "Res3") (field (name "PUBLISHER") "Altium Limited"))
      (libsource (lib "Miscellaneous Devices") (part "Res3"))
    )
    (comp (ref "R424")
      (value "20")
      (footprint "R0402")
      (description "Resistor")
      (fields (field (name "Comment") "Res3") (field (name "PUBLISHER") "Altium Limited"))
      (libsource (lib "Miscellaneous Devices") (part "Res3"))
    )
    (comp (ref "R425")
      (value "20")
      (footprint "R0402")
      (description "Resistor")
      (fields (field (name "Comment") "Res3") (field (name "PUBLISHER") "Altium Limited"))
      (libsource (lib "Miscellaneous Devices") (part "Res3"))
    )
    (comp (ref "R426")
      (value "20")
      (footprint "R0402")
      (description "Resistor")
      (fields (field (name "Comment") "Res3") (field (name "PUBLISHER") "Altium Limited"))
      (libsource (lib "Miscellaneous Devices") (part "Res3"))
    )
    (comp (ref "R427")
      (value "20")
      (footprint "R0402")
      (description "Resistor")
      (fields (field (name "Comment") "Res3") (field (name "PUBLISHER") "Altium Limited"))
      (libsource (lib "Miscellaneous Devices") (part "Res3"))
    )
    (comp (ref "R428")
      (value "20")
      (footprint "R0402")
      (description "Resistor")
      (fields (field (name "Comment") "Res3") (field (name "PUBLISHER") "Altium Limited"))
      (libsource (lib "Miscellaneous Devices") (part "Res3"))
    )
    (comp (ref "R429")
      (value "20")
      (footprint "R0402")
      (description "Resistor")
      (fields (field (name "Comment") "Res3") (field (name "PUBLISHER") "Altium Limited"))
      (libsource (lib "Miscellaneous Devices") (part "Res3"))
    )
    (comp (ref "R430")
      (value "20")
      (footprint "R0402")
      (description "Resistor")
      (fields (field (name "Comment") "Res3") (field (name "PUBLISHER") "Altium Limited"))
      (libsource (lib "Miscellaneous Devices") (part "Res3"))
    )
    (comp (ref "R431")
      (value "20")
      (footprint "R0402")
      (description "Resistor")
      (fields (field (name "Comment") "Res3") (field (name "PUBLISHER") "Altium Limited"))
      (libsource (lib "Miscellaneous Devices") (part "Res3"))
    )
    (comp (ref "R432")
      (value "20")
      (footprint "R0402")
      (description "Resistor")
      (fields (field (name "Comment") "Res3") (field (name "PUBLISHER") "Altium Limited"))
      (libsource (lib "Miscellaneous Devices") (part "Res3"))
    )
    (comp (ref "R433")
      (value "20")
      (footprint "R0402")
      (description "Resistor")
      (fields (field (name "Comment") "Res3") (field (name "PUBLISHER") "Altium Limited"))
      (libsource (lib "Miscellaneous Devices") (part "Res3"))
    )
    (comp (ref "R434")
      (value "20")
      (footprint "R0402")
      (description "Resistor")
      (fields (field (name "Comment") "Res3") (field (name "PUBLISHER") "Altium Limited"))
      (libsource (lib "Miscellaneous Devices") (part "Res3"))
    )
    (comp (ref "R435")
      (value "20")
      (footprint "R0402")
      (description "Resistor")
      (fields (field (name "Comment") "Res3") (field (name "PUBLISHER") "Altium Limited"))
      (libsource (lib "Miscellaneous Devices") (part "Res3"))
    )
    (comp (ref "R436")
      (value "20")
      (footprint "R0402")
      (description "Resistor")
      (fields (field (name "Comment") "Res3") (field (name "PUBLISHER") "Altium Limited"))
      (libsource (lib "Miscellaneous Devices") (part "Res3"))
    )
    (comp (ref "R437")
      (value "20")
      (footprint "R0402")
      (description "Resistor")
      (fields (field (name "Comment") "Res3") (field (name "PUBLISHER") "Altium Limited"))
      (libsource (lib "Miscellaneous Devices") (part "Res3"))
    )
    (comp (ref "R438")
      (value "20")
      (footprint "R0402")
      (description "Resistor")
      (fields (field (name "Comment") "Res3") (field (name "PUBLISHER") "Altium Limited"))
      (libsource (lib "Miscellaneous Devices") (part "Res3"))
    )
    (comp (ref "R439")
      (value "20")
      (footprint "R0402")
      (description "Resistor")
      (fields (field (name "Comment") "Res3") (field (name "PUBLISHER") "Altium Limited"))
      (libsource (lib "Miscellaneous Devices") (part "Res3"))
    )
    (comp (ref "R440")
      (value "20")
      (footprint "R0402")
      (description "Resistor")
      (fields (field (name "Comment") "Res3") (field (name "PUBLISHER") "Altium Limited"))
      (libsource (lib "Miscellaneous Devices") (part "Res3"))
    )
    (comp (ref "U7")
      (value "LTC6269_MS8E")
      (footprint "LTC6269_MSOP8")
      (fields (field (name "SUPPLIER PART NUMBER 1") "LTC6269IMS8E#PBF-ND"))
      (libsource (lib "Lib1") (part "LTC6269_MS8E"))
    )
    (comp (ref "U8")
      (value "LTC6269_MS8E")
      (footprint "LTC6269_MSOP8")
      (fields (field (name "SUPPLIER PART NUMBER 1") "LTC6269IMS8E#PBF-ND"))
      (libsource (lib "Lib1") (part "LTC6269_MS8E"))
    )
    (comp (ref "U9")
      (value "LTC6269_MS8E")
      (footprint "LTC6269_MSOP8")
      (fields (field (name "SUPPLIER PART NUMBER 1") "LTC6269IMS8E#PBF-ND"))
      (libsource (lib "Lib1") (part "LTC6269_MS8E"))
    )
    (comp (ref "U10")
      (value "LTC6269_MS8E")
      (footprint "LTC6269_MSOP8")
      (fields (field (name "SUPPLIER PART NUMBER 1") "LTC6269IMS8E#PBF-ND"))
      (libsource (lib "Lib1") (part "LTC6269_MS8E"))
    )
    (comp (ref "U11")
      (value "LTC6269_MS8E")
      (footprint "LTC6269_MSOP8")
      (fields (field (name "SUPPLIER PART NUMBER 1") "LTC6269IMS8E#PBF-ND"))
      (libsource (lib "Lib1") (part "LTC6269_MS8E"))
    )
    (comp (ref "U12")
      (value "LTC6269_MS8E")
      (footprint "LTC6269_MSOP8")
      (fields (field (name "SUPPLIER PART NUMBER 1") "LTC6269IMS8E#PBF-ND"))
      (libsource (lib "Lib1") (part "LTC6269_MS8E"))
    )
    (comp (ref "U13")
      (value "LTC6269_MS8E")
      (footprint "LTC6269_MSOP8")
      (fields (field (name "SUPPLIER PART NUMBER 1") "LTC6269IMS8E#PBF-ND"))
      (libsource (lib "Lib1") (part "LTC6269_MS8E"))
    )
    (comp (ref "U14")
      (value "LTC6269_MS8E")
      (footprint "LTC6269_MSOP8")
      (fields (field (name "SUPPLIER PART NUMBER 1") "LTC6269IMS8E#PBF-ND"))
      (libsource (lib "Lib1") (part "LTC6269_MS8E"))
    )
    (comp (ref "U15")
      (value "OP193_SOIC8")
      (footprint "OP193_SOIC8")
      (fields (field (name "SUPPLIER PART NUMBER 1") "OP193FSZ-REEL7CT-ND"))
      (libsource (lib "Lib1") (part "OP193_SOIC8"))
    )
    (comp (ref "U16")
      (value "AD1580_SOT23_3")
      (footprint "AD1580_SOT23_3")
      (fields (field (name "SUPPLIER PART NUMBER 1") "AD1580BRTZ-REEL7CT-ND"))
      (libsource (lib "Lib1") (part "AD1580_SOT23_3"))
    )
    (comp (ref "U17")
      (value "ADC7125_LQFP48")
      (footprint "ADV7125_LQFP48")
      (fields (field (name "SUPPLIER PART NUMBER 1") "ADV7125KSTZ140-ND"))
      (libsource (lib "Lib1") (part "ADC7125_LQFP48"))
    )
    (comp (ref "U18")
      (value "ADC7125_LQFP48")
      (footprint "ADV7125_LQFP48")
      (fields (field (name "SUPPLIER PART NUMBER 1") "ADV7125KSTZ140-ND"))
      (libsource (lib "Lib1") (part "ADC7125_LQFP48"))
    )
    (comp (ref "U19")
      (value "ADC7125_LQFP48")
      (footprint "ADV7125_LQFP48")
      (fields (field (name "SUPPLIER PART NUMBER 1") "ADV7125KSTZ140-ND"))
      (libsource (lib "Lib1") (part "ADC7125_LQFP48"))
    )
  )
  (nets
    (net (code "1") (name "/A3V3") (class "Default")
      (node (ref "C153") (pin "1") (pinfunction "1_1") (pintype "passive"))
      (node (ref "C154") (pin "1") (pinfunction "1_1") (pintype "passive"))
      (node (ref "C155") (pin "1") (pinfunction "1_1") (pintype "passive"))
      (node (ref "C156") (pin "1") (pinfunction "1_1") (pintype "passive"))
      (node (ref "C157") (pin "1") (pinfunction "1_1") (pintype "passive"))
      (node (ref "C158") (pin "1") (pinfunction "1_1") (pintype "passive"))
      (node (ref "C38") (pin "1") (pinfunction "1_1") (pintype "passive"))
      (node (ref "C39") (pin "1") (pinfunction "1_1") (pintype "passive"))
      (node (ref "U10") (pin "8") (pinfunction "V+_8") (pintype "passive"))
      (node (ref "U11") (pin "8") (pinfunction "V+_8") (pintype "passive"))
      (node (ref "U12") (pin "8") (pinfunction "V+_8") (pintype "passive"))
      (node (ref "U13") (pin "8") (pinfunction "V+_8") (pintype "passive"))
      (node (ref "U14") (pin "8") (pinfunction "V+_8") (pintype "passive"))
      (node (ref "U7") (pin "8") (pinfunction "V+_8") (pintype "passive"))
      (node (ref "U8") (pin "8") (pinfunction "V+_8") (pintype "passive"))
      (node (ref "U9") (pin "8") (pinfunction "V+_8") (pintype "passive"))
    )
    (net (code "2") (name "/CLK") (class "Default")
      (node (ref "R238") (pin "2") (pinfunction "2_2") (pintype "passive"))
      (node (ref "R375") (pin "2") (pinfunction "2_2") (pintype "passive"))
      (node (ref "R376") (pin "2") (pinfunction "2_2") (pintype "passive"))
    )
    (net (code "3") (name "/COMP1") (class "Default")
      (node (ref "C57") (pin "1") (pinfunction "1_1") (pintype "passive"))
      (node (ref "U17") (pin "35") (pinfunction "COMP_35") (pintype "passive"))
    )
    (net (code "4") (name "/COMP2") (class "Default")
      (node (ref "C58") (pin "1") (pinfunction "1_1") (pintype "passive"))
      (node (ref "U18") (pin "35") (pinfunction "COMP_35") (pintype "passive"))
    )
    (net (code "5") (name "/COMP3") (class "Default")
      (node (ref "C59") (pin "1") (pinfunction "1_1") (pintype "passive"))
      (node (ref "U19") (pin "35") (pinfunction "COMP_35") (pintype "passive"))
    )
    (net (code "6") (name "/D3V3") (class "Default")
      (node (ref "C159") (pin "1") (pinfunction "1_1") (pintype "passive"))
      (node (ref "C160") (pin "1") (pinfunction "1_1") (pintype "passive"))
      (node (ref "C161") (pin "1") (pinfunction "1_1") (pintype "passive"))
      (node (ref "C162") (pin "1") (pinfunction "1_1") (pintype "passive"))
      (node (ref "C163") (pin "1") (pinfunction "1_1") (pintype "passive"))
      (node (ref "C164") (pin "1") (pinfunction "1_1") (pintype "passive"))
      (node (ref "C165") (pin "1") (pinfunction "1_1") (pintype "passive"))
      (node (ref "C166") (pin "1") (pinfunction "1_1") (pintype "passive"))
      (node (ref "C167") (pin "1") (pinfunction "1_1") (pintype "passive"))
      (node (ref "C168") (pin "1") (pinfunction "1_1") (pintype "passive"))
      (node (ref "C51") (pin "1") (pinfunction "1_1") (pintype "passive"))
      (node (ref "C52") (pin "1") (pinfunction "1_1") (pintype "passive"))
      (node (ref "C53") (pin "1") (pinfunction "1_1") (pintype "passive"))
      (node (ref "C54") (pin "1") (pinfunction "1_1") (pintype "passive"))
      (node (ref "C55") (pin "1") (pinfunction "1_1") (pintype "passive"))
      (node (ref "C56") (pin "1") (pinfunction "1_1") (pintype "passive"))
      (node (ref "C57") (pin "2") (pinfunction "2_2") (pintype "passive"))
      (node (ref "C58") (pin "2") (pinfunction "2_2") (pintype "passive"))
      (node (ref "C59") (pin "2") (pinfunction "2_2") (pintype "passive"))
      (node (ref "C61") (pin "1") (pinfunction "1_1") (pintype "passive"))
      (node (ref "C62") (pin "1") (pinfunction "1_1") (pintype "passive"))
      (node (ref "C63") (pin "1") (pinfunction "1_1") (pintype "passive"))
      (node (ref "R146") (pin "2") (pinfunction "2_2") (pintype "passive"))
      (node (ref "U15") (pin "7") (pinfunction "V+_7") (pintype "passive"))
      (node (ref "U17") (pin "11") (pinfunction "~{BLANK}_11") (pintype "passive"))
      (node (ref "U17") (pin "13") (pinfunction "VAA_13") (pintype "passive"))
      (node (ref "U17") (pin "29") (pinfunction "VAA_29") (pintype "passive"))
      (node (ref "U17") (pin "30") (pinfunction "VAA_30") (pintype "passive"))
      (node (ref "U18") (pin "11") (pinfunction "~{BLANK}_11") (pintype "passive"))
      (node (ref "U18") (pin "13") (pinfunction "VAA_13") (pintype "passive"))
      (node (ref "U18") (pin "29") (pinfunction "VAA_29") (pintype "passive"))
      (node (ref "U18") (pin "30") (pinfunction "VAA_30") (pintype "passive"))
      (node (ref "U19") (pin "11") (pinfunction "~{BLANK}_11") (pintype "passive"))
      (node (ref "U19") (pin "13") (pinfunction "VAA_13") (pintype "passive"))
      (node (ref "U19") (pin "29") (pinfunction "VAA_29") (pintype "passive"))
      (node (ref "U19") (pin "30") (pinfunction "VAA_30") (pintype "passive"))
    )
    (net (code "7") (name "/GND") (class "Default")
      (node (ref "C153") (pin "2") (pinfunction "2_2") (pintype "passive"))
      (node (ref "C154") (pin "2") (pinfunction "2_2") (pintype "passive"))
      (node (ref "C155") (pin "2") (pinfunction "2_2") (pintype "passive"))
      (node (ref "C156") (pin "2") (pinfunction "2_2") (pintype "passive"))
      (node (ref "C157") (pin "2") (pinfunction "2_2") (pintype "passive"))
      (node (ref "C158") (pin "2") (pinfunction "2_2") (pintype "passive"))
      (node (ref "C159") (pin "2") (pinfunction "2_2") (pintype "passive"))
      (node (ref "C160") (pin "2") (pinfunction "2_2") (pintype "passive"))
      (node (ref "C161") (pin "2") (pinfunction "2_2") (pintype "passive"))
      (node (ref "C162") (pin "2") (pinfunction "2_2") (pintype "passive"))
      (node (ref "C163") (pin "2") (pinfunction "2_2") (pintype "passive"))
      (node (ref "C164") (pin "2") (pinfunction "2_2") (pintype "passive"))
      (node (ref "C165") (pin "2") (pinfunction "2_2") (pintype "passive"))
      (node (ref "C166") (pin "2") (pinfunction "2_2") (pintype "passive"))
      (node (ref "C167") (pin "2") (pinfunction "2_2") (pintype "passive"))
      (node (ref "C168") (pin "2") (pinfunction "2_2") (pintype "passive"))
      (node (ref "C38") (pin "2") (pinfunction "2_2") (pintype "passive"))
      (node (ref "C39") (pin "2") (pinfunction "2_2") (pintype "passive"))
      (node (ref "C50") (pin "2") (pinfunction "2_2") (pintype "passive"))
      (node (ref "C51") (pin "2") (pinfunction "2_2") (pintype "passive"))
      (node (ref "C52") (pin "2") (pinfunction "2_2") (pintype "passive"))
      (node (ref "C53") (pin "2") (pinfunction "2_2") (pintype "passive"))
      (node (ref "C54") (pin "2") (pinfunction "2_2") (pintype "passive"))
      (node (ref "C55") (pin "2") (pinfunction "2_2") (pintype "passive"))
      (node (ref "C56") (pin "2") (pinfunction "2_2") (pintype "passive"))
      (node (ref "C60") (pin "1") (pinfunction "1_1") (pintype "passive"))
      (node (ref "C61") (pin "2") (pinfunction "2_2") (pintype "passive"))
      (node (ref "C62") (pin "2") (pinfunction "2_2") (pintype "passive"))
      (node (ref "C63") (pin "2") (pinfunction "2_2") (pintype "passive"))
      (node (ref "P17") (pin "1") (pinfunction "1_1") (pintype "passive"))
      (node (ref "R102") (pin "1") (pinfunction "1_1") (pintype "passive"))
      (node (ref "R103") (pin "1") (pinfunction "1_1") (pintype "passive"))
      (node (ref "R104") (pin "1") (pinfunction "1_1") (pintype "passive"))
      (node (ref "R105") (pin "1") (pinfunction "1_1") (pintype "passive"))
      (node (ref "R106") (pin "1") (pinfunction "1_1") (pintype "passive"))
      (node (ref "R107") (pin "1") (pinfunction "1_1") (pintype "passive"))
      (node (ref "R108") (pin "1") (pinfunction "1_1") (pintype "passive"))
      (node (ref "R109") (pin "1") (pinfunction "1_1") (pintype "passive"))
      (node (ref "R114") (pin "1") (pinfunction "1_1") (pintype "passive"))
      (node (ref "R115") (pin "1") (pinfunction "1_1") (pintype "passive"))
      (node (ref "R116") (pin "1") (pinfunction "1_1") (pintype "passive"))
      (node (ref "R117") (pin "1") (pinfunction "1_1") (pintype "passive"))
      (node (ref "R118") (pin "1") (pinfunction "1_1") (pintype "passive"))
      (node (ref "R119") (pin "1") (pinfunction "1_1") (pintype "passive"))
      (node (ref "R120") (pin "1") (pinfunction "1_1") (pintype "passive"))
      (node (ref "R121") (pin "1") (pinfunction "1_1") (pintype "passive"))
      (node (ref "R126") (pin "1") (pinfunction "1_1") (pintype "passive"))
      (node (ref "R127") (pin "1") (pinfunction "1_1") (pintype "passive"))
      (node (ref "R128") (pin "1") (pinfunction "1_1") (pintype "passive"))
      (node (ref "R129") (pin "1") (pinfunction "1_1") (pintype "passive"))
      (node (ref "R130") (pin "1") (pinfunction "1_1") (pintype "passive"))
      (node (ref "R131") (pin "1") (pinfunction "1_1") (pintype "passive"))
      (node (ref "R132") (pin "1") (pinfunction "1_1") (pintype "passive"))
      (node (ref "R133") (pin "1") (pinfunction "1_1") (pintype "passive"))
      (node (ref "R138") (pin "1") (pinfunction "1_1") (pintype "passive"))
      (node (ref "R139") (pin "1") (pinfunction "1_1") (pintype "passive"))
      (node (ref "R140") (pin "1") (pinfunction "1_1") (pintype "passive"))
      (node (ref "R141") (pin "1") (pinfunction "1_1") (pintype "passive"))
      (node (ref "R142") (pin "1") (pinfunction "1_1") (pintype "passive"))
      (node (ref "R143") (pin "1") (pinfunction "1_1") (pintype "passive"))
      (node (ref "R144") (pin "1") (pinfunction "1_1") (pintype "passive"))
      (node (ref "R145") (pin "1") (pinfunction "1_1") (pintype "passive"))
      (node (ref "R148") (pin "1") (pinfunction "1_1") (pintype "passive"))
      (node (ref "R149") (pin "1") (pinfunction "1_1") (pintype "passive"))
      (node (ref "R150") (pin "1") (pinfunction "1_1") (pintype "passive"))
      (node (ref "R151") (pin "1") (pinfunction "1_1") (pintype "passive"))
      (node (ref "R152") (pin "1") (pinfunction "1_1") (pintype "passive"))
      (node (ref "U15") (pin "4") (pinfunction "V-_4") (pintype "passive"))
      (node (ref "U16") (pin "2") (pinfunction "V-_2") (pintype "passive"))
      (node (ref "U17") (pin "1") (pinfunction "GND_1") (pintype "passive"))
      (node (ref "U17") (pin "12") (pinfunction "~{SYNC}_12") (pintype "passive"))
      (node (ref "U17") (pin "14") (pinfunction "GND_14") (pintype "passive"))
      (node (ref "U17") (pin "15") (pinfunction "GND_15") (pintype "passive"))
      (node (ref "U17") (pin "2") (pinfunction "GND_2") (pintype "passive"))
      (node (ref "U17") (pin "25") (pinfunction "GND_25") (pintype "passive"))
      (node (ref "U17") (pin "26") (pinfunction "GND_26") (pintype "passive"))
      (node (ref "U17") (pin "39") (pinfunction "GND_39") (pintype "passive"))
      (node (ref "U17") (pin "40") (pinfunction "GND_40") (pintype "passive"))
      (node (ref "U18") (pin "1") (pinfunction "GND_1") (pintype "passive"))
      (node (ref "U18") (pin "12") (pinfunction "~{SYNC}_12") (pintype "passive"))
      (node (ref "U18") (pin "14") (pinfunction "GND_14") (pintype "passive"))
      (node (ref "U18") (pin "15") (pinfunction "GND_15") (pintype "passive"))
      (node (ref "U18") (pin "2") (pinfunction "GND_2") (pintype "passive"))
      (node (ref "U18") (pin "25") (pinfunction "GND_25") (pintype "passive"))
      (node (ref "U18") (pin "26") (pinfunction "GND_26") (pintype "passive"))
      (node (ref "U18") (pin "39") (pinfunction "GND_39") (pintype "passive"))
      (node (ref "U18") (pin "40") (pinfunction "GND_40") (pintype "passive"))
      (node (ref "U19") (pin "1") (pinfunction "GND_1") (pintype "passive"))
      (node (ref "U19") (pin "12") (pinfunction "~{SYNC}_12") (pintype "passive"))
      (node (ref "U19") (pin "14") (pinfunction "GND_14") (pintype "passive"))
      (node (ref "U19") (pin "15") (pinfunction "GND_15") (pintype "passive"))
      (node (ref "U19") (pin "16") (pinfunction "B0_16") (pintype "passive"))
      (node (ref "U19") (pin "17") (pinfunction "B1_17") (pintype "passive"))
      (node (ref "U19") (pin "18") (pinfunction "B2_18") (pintype "passive"))
      (node (ref "U19") (pin "19") (pinfunction "B3_19") (pintype "passive"))
      (node (ref "U19") (pin "2") (pinfunction "GND_2") (pintype "passive"))
      (node (ref "U19") (pin "20") (pinfunction "B4_20") (pintype "passive"))
      (node (ref "U19") (pin "21") (pinfunction "B5_21") (pintype "passive"))
      (node (ref "U19") (pin "22") (pinfunction "B6_22") (pintype "passive"))
      (node (ref "U19") (pin "23") (pinfunction "B7_23") (pintype "passive"))
      (node (ref "U19") (pin "25") (pinfunction "GND_25") (pintype "passive"))
      (node (ref "U19") (pin "26") (pinfunction "GND_26") (pintype "passive"))
      (node (ref "U19") (pin "39") (pinfunction "GND_39") (pintype "passive"))
      (node (ref "U19") (pin "40") (pinfunction "GND_40") (pintype "passive"))
    )
    (net (code "8") (name "/IN1M") (class "Default")
      (node (ref "R105") (pin "2") (pinfunction "2_2") (pintype "passive"))
      (node (ref "R99") (pin "1") (pinfunction "TOP_1") (pintype "passive"))
      (node (ref "U7") (pin "6") (pinfunction "-INB_6") (pintype "passive"))
    )
    (net (code "9") (name "/IN1P") (class "Default")
      (node (ref "R104") (pin "2") (pinfunction "2_2") (pintype "passive"))
      (node (ref "R98") (pin "1") (pinfunction "TOP_1") (pintype "passive"))
      (node (ref "U7") (pin "2") (pinfunction "-INA_2") (pintype "passive"))
    )
    (net (code "11") (name "/IN2M") (class "Default")
      (node (ref "R111") (pin "1") (pinfunction "TOP_1") (pintype "passive"))
      (node (ref "R117") (pin "2") (pinfunction "2_2") (pintype "passive"))
      (node (ref "U8") (pin "6") (pinfunction "-INB_6") (pintype "passive"))
    )
    (net (code "12") (name "/IN2P") (class "Default")
      (node (ref "R110") (pin "1") (pinfunction "TOP_1") (pintype "passive"))
      (node (ref "R116") (pin "2") (pinfunction "2_2") (pintype "passive"))
      (node (ref "U8") (pin "2") (pinfunction "-INA_2") (pintype "passive"))
    )
    (net (code "14") (name "/IN3M") (class "Default")
      (node (ref "R123") (pin "1") (pinfunction "TOP_1") (pintype "passive"))
      (node (ref "R129") (pin "2") (pinfunction "2_2") (pintype "passive"))
      (node (ref "U9") (pin "6") (pinfunction "-INB_6") (pintype "passive"))
    )
    (net (code "15") (name "/IN3P") (class "Default")
      (node (ref "R122") (pin "1") (pinfunction "TOP_1") (pintype "passive"))
      (node (ref "R128") (pin "2") (pinfunction "2_2") (pintype "passive"))
      (node (ref "U9") (pin "2") (pinfunction "-INA_2") (pintype "passive"))
    )
    (net (code "17") (name "/IN4M") (class "Default")
      (node (ref "R135") (pin "1") (pinfunction "TOP_1") (pintype "passive"))
      (node (ref "R141") (pin "2") (pinfunction "2_2") (pintype "passive"))
      (node (ref "U10") (pin "6") (pinfunction "-INB_6") (pintype "passive"))
    )
    (net (code "18") (name "/IN4P") (class "Default")
      (node (ref "R134") (pin "1") (pinfunction "TOP_1") (pintype "passive"))
      (node (ref "R140") (pin "2") (pinfunction "2_2") (pintype "passive"))
      (node (ref "U10") (pin "2") (pinfunction "-INA_2") (pintype "passive"))
    )
    (net (code "20") (name "/IN5M") (class "Default")
      (node (ref "R101") (pin "1") (pinfunction "TOP_1") (pintype "passive"))
      (node (ref "R109") (pin "2") (pinfunction "2_2") (pintype "passive"))
      (node (ref "U11") (pin "6") (pinfunction "-INB_6") (pintype "passive"))
    )
    (net (code "21") (name "/IN5P") (class "Default")
      (node (ref "R100") (pin "1") (pinfunction "TOP_1") (pintype "passive"))
      (node (ref "R108") (pin "2") (pinfunction "2_2") (pintype "passive"))
      (node (ref "U11") (pin "2") (pinfunction "-INA_2") (pintype "passive"))
    )
    (net (code "23") (name "/IN6M") (class "Default")
      (node (ref "R113") (pin "1") (pinfunction "TOP_1") (pintype "passive"))
      (node (ref "R121") (pin "2") (pinfunction "2_2") (pintype "passive"))
      (node (ref "U12") (pin "6") (pinfunction "-INB_6") (pintype "passive"))
    )
    (net (code "24") (name "/IN6P") (class "Default")
      (node (ref "R112") (pin "1") (pinfunction "TOP_1") (pintype "passive"))
      (node (ref "R120") (pin "2") (pinfunction "2_2") (pintype "passive"))
      (node (ref "U12") (pin "2") (pinfunction "-INA_2") (pintype "passive"))
    )
    (net (code "26") (name "/IN7M") (class "Default")
      (node (ref "R125") (pin "1") (pinfunction "TOP_1") (pintype "passive"))
      (node (ref "R133") (pin "2") (pinfunction "2_2") (pintype "passive"))
      (node (ref "U13") (pin "6") (pinfunction "-INB_6") (pintype "passive"))
    )
    (net (code "27") (name "/IN7P") (class "Default")
      (node (ref "R124") (pin "1") (pinfunction "TOP_1") (pintype "passive"))
      (node (ref "R132") (pin "2") (pinfunction "2_2") (pintype "passive"))
      (node (ref "U13") (pin "2") (pinfunction "-INA_2") (pintype "passive"))
    )
    (net (code "29") (name "/IN8M") (class "Default")
      (node (ref "R137") (pin "1") (pinfunction "TOP_1") (pintype "passive"))
      (node (ref "R145") (pin "2") (pinfunction "2_2") (pintype "passive"))
      (node (ref "U14") (pin "6") (pinfunction "-INB_6") (pintype "passive"))
    )
    (net (code "30") (name "/IN8P") (class "Default")
      (node (ref "R136") (pin "1") (pinfunction "TOP_1") (pintype "passive"))
      (node (ref "R144") (pin "2") (pinfunction "2_2") (pintype "passive"))
      (node (ref "U14") (pin "2") (pinfunction "-INA_2") (pintype "passive"))
    )
    (net (code "32") (name "/IN10") (class "Default")
      (node (ref "R419") (pin "1") (pinfunction "1_1") (pintype "passive"))
    )
    (net (code "33") (name "/IN11") (class "Default")
      (node (ref "R414") (pin "1") (pinfunction "1_1") (pintype "passive"))
    )
    (net (code "34") (name "/IN12") (class "Default")
      (node (ref "R408") (pin "1") (pinfunction "1_1") (pintype "passive"))
    )
    (net (code "35") (name "/IN13") (class "Default")
      (node (ref "R402") (pin "1") (pinfunction "1_1") (pintype "passive"))
    )
    (net (code "36") (name "/IN14") (class "Default")
      (node (ref "R396") (pin "1") (pinfunction "1_1") (pintype "passive"))
    )
    (net (code "37") (name "/IN15") (class "Default")
      (node (ref "R390") (pin "1") (pinfunction "1_1") (pintype "passive"))
    )
    (net (code "38") (name "/IN16") (class "Default")
      (node (ref "R384") (pin "1") (pinfunction "1_1") (pintype "passive"))
    )
    (net (code "39") (name "/IN17") (class "Default")
      (node (ref "R380") (pin "1") (pinfunction "1_1") (pintype "passive"))
    )
    (net (code "40") (name "/IN20") (class "Default")
      (node (ref "R389") (pin "2") (pinfunction "2_2") (pintype "passive"))
    )
    (net (code "41") (name "/IN21") (class "Default")
      (node (ref "R395") (pin "2") (pinfunction "2_2") (pintype "passive"))
    )
    (net (code "42") (name "/IN22") (class "Default")
      (node (ref "R401") (pin "2") (pinfunction "2_2") (pintype "passive"))
    )
    (net (code "43") (name "/IN23") (class "Default")
      (node (ref "R407") (pin "2") (pinfunction "2_2") (pintype "passive"))
    )
    (net (code "44") (name "/IN24") (class "Default")
      (node (ref "R413") (pin "2") (pinfunction "2_2") (pintype "passive"))
    )
    (net (code "45") (name "/IN25") (class "Default")
      (node (ref "R418") (pin "2") (pinfunction "2_2") (pintype "passive"))
    )
    (net (code "46") (name "/IN26") (class "Default")
      (node (ref "R422") (pin "2") (pinfunction "2_2") (pintype "passive"))
    )
    (net (code "47") (name "/IN27") (class "Default")
      (node (ref "R424") (pin "2") (pinfunction "2_2") (pintype "passive"))
    )
    (net (code "48") (name "/IN30") (class "Default")
      (node (ref "R426") (pin "2") (pinfunction "2_2") (pintype "passive"))
    )
    (net (code "49") (name "/IN31") (class "Default")
      (node (ref "R428") (pin "2") (pinfunction "2_2") (pintype "passive"))
    )
    (net (code "50") (name "/IN32") (class "Default")
      (node (ref "R430") (pin "2") (pinfunction "2_2") (pintype "passive"))
    )
    (net (code "51") (name "/IN33") (class "Default")
      (node (ref "R432") (pin "2") (pinfunction "2_2") (pintype "passive"))
    )
    (net (code "52") (name "/IN34") (class "Default")
      (node (ref "R434") (pin "2") (pinfunction "2_2") (pintype "passive"))
    )
    (net (code "53") (name "/IN35") (class "Default")
      (node (ref "R436") (pin "2") (pinfunction "2_2") (pintype "passive"))
    )
    (net (code "54") (name "/IN36") (class "Default")
      (node (ref "R438") (pin "2") (pinfunction "2_2") (pintype "passive"))
    )
    (net (code "55") (name "/IN37") (class "Default")
      (node (ref "R440") (pin "2") (pinfunction "2_2") (pintype "passive"))
    )
    (net (code "56") (name "/IN40") (class "Default")
      (node (ref "R416") (pin "1") (pinfunction "1_1") (pintype "passive"))
    )
    (net (code "57") (name "/IN41") (class "Default")
      (node (ref "R410") (pin "1") (pinfunction "1_1") (pintype "passive"))
    )
    (net (code "58") (name "/IN42") (class "Default")
      (node (ref "R404") (pin "1") (pinfunction "1_1") (pintype "passive"))
    )
    (net (code "59") (name "/IN43") (class "Default")
      (node (ref "R398") (pin "1") (pinfunction "1_1") (pintype "passive"))
    )
    (net (code "60") (name "/IN44") (class "Default")
      (node (ref "R392") (pin "1") (pinfunction "1_1") (pintype "passive"))
    )
    (net (code "61") (name "/IN45") (class "Default")
      (node (ref "R386") (pin "1") (pinfunction "1_1") (pintype "passive"))
    )
    (net (code "62") (name "/IN46") (class "Default")
      (node (ref "R381") (pin "1") (pinfunction "1_1") (pintype "passive"))
    )
    (net (code "63") (name "/IN47") (class "Default")
      (node (ref "R378") (pin "1") (pinfunction "1_1") (pintype "passive"))
    )
    (net (code "64") (name "/IN50") (class "Default")
      (node (ref "R385") (pin "2") (pinfunction "2_2") (pintype "passive"))
    )
    (net (code "65") (name "/IN51") (class "Default")
      (node (ref "R391") (pin "2") (pinfunction "2_2") (pintype "passive"))
    )
    (net (code "66") (name "/IN52") (class "Default")
      (node (ref "R397") (pin "2") (pinfunction "2_2") (pintype "passive"))
    )
    (net (code "67") (name "/IN53") (class "Default")
      (node (ref "R403") (pin "2") (pinfunction "2_2") (pintype "passive"))
    )
    (net (code "68") (name "/IN54") (class "Default")
      (node (ref "R409") (pin "2") (pinfunction "2_2") (pintype "passive"))
    )
    (net (code "69") (name "/IN55") (class "Default")
      (node (ref "R415") (pin "2") (pinfunction "2_2") (pintype "passive"))
    )
    (net (code "70") (name "/IN56") (class "Default")
      (node (ref "R420") (pin "2") (pinfunction "2_2") (pintype "passive"))
    )
    (net (code "71") (name "/IN57") (class "Default")
      (node (ref "R423") (pin "2") (pinfunction "2_2") (pintype "passive"))
    )
    (net (code "72") (name "/IN60") (class "Default")
      (node (ref "R425") (pin "2") (pinfunction "2_2") (pintype "passive"))
    )
    (net (code "73") (name "/IN61") (class "Default")
      (node (ref "R427") (pin "2") (pinfunction "2_2") (pintype "passive"))
    )
    (net (code "74") (name "/IN62") (class "Default")
      (node (ref "R429") (pin "2") (pinfunction "2_2") (pintype "passive"))
    )
    (net (code "75") (name "/IN63") (class "Default")
      (node (ref "R431") (pin "2") (pinfunction "2_2") (pintype "passive"))
    )
    (net (code "76") (name "/IN64") (class "Default")
      (node (ref "R433") (pin "2") (pinfunction "2_2") (pintype "passive"))
    )
    (net (code "77") (name "/IN65") (class "Default")
      (node (ref "R435") (pin "2") (pinfunction "2_2") (pintype "passive"))
    )
    (net (code "78") (name "/IN66") (class "Default")
      (node (ref "R437") (pin "2") (pinfunction "2_2") (pintype "passive"))
    )
    (net (code "79") (name "/IN67") (class "Default")
      (node (ref "R439") (pin "2") (pinfunction "2_2") (pintype "passive"))
    )
    (net (code "80") (name "/IN70") (class "Default")
      (node (ref "R412") (pin "1") (pinfunction "1_1") (pintype "passive"))
    )
    (net (code "81") (name "/IN71") (class "Default")
      (node (ref "R406") (pin "1") (pinfunction "1_1") (pintype "passive"))
    )
    (net (code "82") (name "/IN72") (class "Default")
      (node (ref "R400") (pin "1") (pinfunction "1_1") (pintype "passive"))
    )
    (net (code "83") (name "/IN73") (class "Default")
      (node (ref "R394") (pin "1") (pinfunction "1_1") (pintype "passive"))
    )
    (net (code "84") (name "/IN74") (class "Default")
      (node (ref "R388") (pin "1") (pinfunction "1_1") (pintype "passive"))
    )
    (net (code "85") (name "/IN75") (class "Default")
      (node (ref "R383") (pin "1") (pinfunction "1_1") (pintype "passive"))
    )
    (net (code "86") (name "/IN76") (class "Default")
      (node (ref "R379") (pin "1") (pinfunction "1_1") (pintype "passive"))
    )
    (net (code "87") (name "/IN77") (class "Default")
      (node (ref "R377") (pin "1") (pinfunction "1_1") (pintype "passive"))
    )
    (net (code "88") (name "/IN80") (class "Default")
      (node (ref "R382") (pin "2") (pinfunction "2_2") (pintype "passive"))
    )
    (net (code "89") (name "/IN81") (class "Default")
      (node (ref "R387") (pin "2") (pinfunction "2_2") (pintype "passive"))
    )
    (net (code "90") (name "/IN82") (class "Default")
      (node (ref "R393") (pin "2") (pinfunction "2_2") (pintype "passive"))
    )
    (net (code "91") (name "/IN83") (class "Default")
      (node (ref "R399") (pin "2") (pinfunction "2_2") (pintype "passive"))
    )
    (net (code "92") (name "/IN84") (class "Default")
      (node (ref "R405") (pin "2") (pinfunction "2_2") (pintype "passive"))
    )
    (net (code "93") (name "/IN85") (class "Default")
      (node (ref "R411") (pin "2") (pinfunction "2_2") (pintype "passive"))
    )
    (net (code "94") (name "/IN86") (class "Default")
      (node (ref "R417") (pin "2") (pinfunction "2_2") (pintype "passive"))
    )
    (net (code "95") (name "/IN87") (class "Default")
      (node (ref "R421") (pin "2") (pinfunction "2_2") (pintype "passive"))
    )
    (net (code "96") (name "/IO1M") (class "Default")
      (node (ref "R103") (pin "2") (pinfunction "2_2") (pintype "passive"))
      (node (ref "U17") (pin "33") (pinfunction "~{IOR}_33") (pintype "passive"))
      (node (ref "U7") (pin "5") (pinfunction "+INB_5") (pintype "passive"))
    )
    (net (code "97") (name "/IO1P") (class "Default")
      (node (ref "R102") (pin "2") (pinfunction "2_2") (pintype "passive"))
      (node (ref "U17") (pin "34") (pinfunction "IOR_34") (pintype "passive"))
      (node (ref "U7") (pin "3") (pinfunction "+INA_3") (pintype "passive"))
    )
    (net (code "98") (name "/IO2M") (class "Default")
      (node (ref "R115") (pin "2") (pinfunction "2_2") (pintype "passive"))
      (node (ref "U17") (pin "31") (pinfunction "~{IOG}_31") (pintype "passive"))
      (node (ref "U8") (pin "5") (pinfunction "+INB_5") (pintype "passive"))
    )
    (net (code "99") (name "/IO2P") (class "Default")
      (node (ref "R114") (pin "2") (pinfunction "2_2") (pintype "passive"))
      (node (ref "U17") (pin "32") (pinfunction "IOG_32") (pintype "passive"))
      (node (ref "U8") (pin "3") (pinfunction "+INA_3") (pintype "passive"))
    )
    (net (code "100") (name "/IO3M") (class "Default")
      (node (ref "R127") (pin "2") (pinfunction "2_2") (pintype "passive"))
      (node (ref "U17") (pin "27") (pinfunction "~{IOB}_27") (pintype "passive"))
      (node (ref "U9") (pin "5") (pinfunction "+INB_5") (pintype "passive"))
    )
    (net (code "101") (name "/IO3P") (class "Default")
      (node (ref "R126") (pin "2") (pinfunction "2_2") (pintype "passive"))
      (node (ref "U17") (pin "28") (pinfunction "IOB_28") (pintype "passive"))
      (node (ref "U9") (pin "3") (pinfunction "+INA_3") (pintype "passive"))
    )
    (net (code "102") (name "/IO4M") (class "Default")
      (node (ref "R139") (pin "2") (pinfunction "2_2") (pintype "passive"))
      (node (ref "U10") (pin "5") (pinfunction "+INB_5") (pintype "passive"))
      (node (ref "U18") (pin "33") (pinfunction "~{IOR}_33") (pintype "passive"))
    )
    (net (code "103") (name "/IO4P") (class "Default")
      (node (ref "R138") (pin "2") (pinfunction "2_2") (pintype "passive"))
      (node (ref "U10") (pin "3") (pinfunction "+INA_3") (pintype "passive"))
      (node (ref "U18") (pin "34") (pinfunction "IOR_34") (pintype "passive"))
    )
    (net (code "104") (name "/IO5M") (class "Default")
      (node (ref "R107") (pin "2") (pinfunction "2_2") (pintype "passive"))
      (node (ref "U11") (pin "5") (pinfunction "+INB_5") (pintype "passive"))
      (node (ref "U18") (pin "31") (pinfunction "~{IOG}_31") (pintype "passive"))
    )
    (net (code "105") (name "/IO5P") (class "Default")
      (node (ref "R106") (pin "2") (pinfunction "2_2") (pintype "passive"))
      (node (ref "U11") (pin "3") (pinfunction "+INA_3") (pintype "passive"))
      (node (ref "U18") (pin "32") (pinfunction "IOG_32") (pintype "passive"))
    )
    (net (code "106") (name "/IO6M") (class "Default")
      (node (ref "R119") (pin "2") (pinfunction "2_2") (pintype "passive"))
      (node (ref "U12") (pin "5") (pinfunction "+INB_5") (pintype "passive"))
      (node (ref "U18") (pin "27") (pinfunction "~{IOB}_27") (pintype "passive"))
    )
    (net (code "107") (name "/IO6P") (class "Default")
      (node (ref "R118") (pin "2") (pinfunction "2_2") (pintype "passive"))
      (node (ref "U12") (pin "3") (pinfunction "+INA_3") (pintype "passive"))
      (node (ref "U18") (pin "28") (pinfunction "IOB_28") (pintype "passive"))
    )
    (net (code "108") (name "/IO7M") (class "Default")
      (node (ref "R131") (pin "2") (pinfunction "2_2") (pintype "passive"))
      (node (ref "U13") (pin "5") (pinfunction "+INB_5") (pintype "passive"))
      (node (ref "U19") (pin "33") (pinfunction "~{IOR}_33") (pintype "passive"))
    )
    (net (code "109") (name "/IO7P") (class "Default")
      (node (ref "R130") (pin "2") (pinfunction "2_2") (pintype "passive"))
      (node (ref "U13") (pin "3") (pinfunction "+INA_3") (pintype "passive"))
      (node (ref "U19") (pin "34") (pinfunction "IOR_34") (pintype "passive"))
    )
    (net (code "110") (name "/IO8M") (class "Default")
      (node (ref "R143") (pin "2") (pinfunction "2_2") (pintype "passive"))
      (node (ref "U14") (pin "5") (pinfunction "+INB_5") (pintype "passive"))
      (node (ref "U19") (pin "31") (pinfunction "~{IOG}_31") (pintype "passive"))
    )
    (net (code "111") (name "/IO8P") (class "Default")
      (node (ref "R142") (pin "2") (pinfunction "2_2") (pintype "passive"))
      (node (ref "U14") (pin "3") (pinfunction "+INA_3") (pintype "passive"))
      (node (ref "U19") (pin "32") (pinfunction "IOG_32") (pintype "passive"))
    )
    (net (code "112") (name "/IO9M") (class "Default")
      (node (ref "R152") (pin "2") (pinfunction "2_2") (pintype "passive"))
      (node (ref "U19") (pin "27") (pinfunction "~{IOB}_27") (pintype "passive"))
    )
    (net (code "113") (name "/IO9P") (class "Default")
      (node (ref "R151") (pin "2") (pinfunction "2_2") (pintype "passive"))
      (node (ref "U19") (pin "28") (pinfunction "IOB_28") (pintype "passive"))
    )
    (net (code "114") (name "/OP193") (class "Default")
      (node (ref "C60") (pin "2") (pinfunction "2_2") (pintype "passive"))
      (node (ref "R147") (pin "2") (pinfunction "2_2") (pintype "passive"))
      (node (ref "U15") (pin "3") (pinfunction "IN+_3") (pintype "passive"))
    )
    (net (code "115") (name "/OUTM1") (class "Default")
      (node (ref "R99") (pin "2") (pinfunction "TAP_2") (pintype "passive"))
      (node (ref "U7") (pin "7") (pinfunction "OUTB_7") (pintype "passive"))
    )
    (net (code "116") (name "/OUTM2") (class "Default")
      (node (ref "R111") (pin "2") (pinfunction "TAP_2") (pintype "passive"))
      (node (ref "U8") (pin "7") (pinfunction "OUTB_7") (pintype "passive"))
    )
    (net (code "117") (name "/OUTM3") (class "Default")
      (node (ref "R123") (pin "2") (pinfunction "TAP_2") (pintype "passive"))
      (node (ref "U9") (pin "7") (pinfunction "OUTB_7") (pintype "passive"))
    )
    (net (code "118") (name "/OUTM4") (class "Default")
      (node (ref "R135") (pin "2") (pinfunction "TAP_2") (pintype "passive"))
      (node (ref "U10") (pin "7") (pinfunction "OUTB_7") (pintype "passive"))
    )
    (net (code "119") (name "/OUTM5") (class "Default")
      (node (ref "R101") (pin "2") (pinfunction "TAP_2") (pintype "passive"))
      (node (ref "U11") (pin "7") (pinfunction "OUTB_7") (pintype "passive"))
    )
    (net (code "120") (name "/OUTM6") (class "Default")
      (node (ref "R113") (pin "2") (pinfunction "TAP_2") (pintype "passive"))
      (node (ref "U12") (pin "7") (pinfunction "OUTB_7") (pintype "passive"))
    )
    (net (code "121") (name "/OUTM7") (class "Default")
      (node (ref "R125") (pin "2") (pinfunction "TAP_2") (pintype "passive"))
      (node (ref "U13") (pin "7") (pinfunction "OUTB_7") (pintype "passive"))
    )
    (net (code "122") (name "/OUTM8") (class "Default")
      (node (ref "R137") (pin "2") (pinfunction "TAP_2") (pintype "passive"))
      (node (ref "U14") (pin "7") (pinfunction "OUTB_7") (pintype "passive"))
    )
    (net (code "124") (name "/OUTP1") (class "Default")
      (node (ref "R98") (pin "2") (pinfunction "TAP_2") (pintype "passive"))
      (node (ref "U7") (pin "1") (pinfunction "OUTA_1") (pintype "passive"))
    )
    (net (code "125") (name "/OUTP2") (class "Default")
      (node (ref "R110") (pin "2") (pinfunction "TAP_2") (pintype "passive"))
      (node (ref "U8") (pin "1") (pinfunction "OUTA_1") (pintype "passive"))
    )
    (net (code "126") (name "/OUTP3") (class "Default")
      (node (ref "R122") (pin "2") (pinfunction "TAP_2") (pintype "passive"))
      (node (ref "U9") (pin "1") (pinfunction "OUTA_1") (pintype "passive"))
    )
    (net (code "127") (name "/OUTP4") (class "Default")
      (node (ref "R134") (pin "2") (pinfunction "TAP_2") (pintype "passive"))
      (node (ref "U10") (pin "1") (pinfunction "OUTA_1") (pintype "passive"))
    )
    (net (code "128") (name "/OUTP5") (class "Default")
      (node (ref "R100") (pin "2") (pinfunction "TAP_2") (pintype "passive"))
      (node (ref "U11") (pin "1") (pinfunction "OUTA_1") (pintype "passive"))
    )
    (net (code "129") (name "/OUTP6") (class "Default")
      (node (ref "R112") (pin "2") (pinfunction "TAP_2") (pintype "passive"))
      (node (ref "U12") (pin "1") (pinfunction "OUTA_1") (pintype "passive"))
    )
    (net (code "130") (name "/OUTP7") (class "Default")
      (node (ref "R124") (pin "2") (pinfunction "TAP_2") (pintype "passive"))
      (node (ref "U13") (pin "1") (pinfunction "OUTA_1") (pintype "passive"))
    )
    (net (code "131") (name "/OUTP8") (class "Default")
      (node (ref "R136") (pin "2") (pinfunction "TAP_2") (pintype "passive"))
      (node (ref "U14") (pin "1") (pinfunction "OUTA_1") (pintype "passive"))
    )
    (net (code "133") (name "/PSAVE1") (class "Default")
      (node (ref "U17") (pin "38") (pinfunction "~{PSAVE}_38") (pintype "passive"))
    )
    (net (code "134") (name "/PSAVE2") (class "Default")
      (node (ref "U18") (pin "38") (pinfunction "~{PSAVE}_38") (pintype "passive"))
    )
    (net (code "135") (name "/PSAVE3") (class "Default")
      (node (ref "U19") (pin "38") (pinfunction "~{PSAVE}_38") (pintype "passive"))
    )
    (net (code "136") (name "/RSET1") (class "Default")
      (node (ref "R148") (pin "2") (pinfunction "2_2") (pintype "passive"))
      (node (ref "U17") (pin "37") (pinfunction "RSET_37") (pintype "passive"))
    )
    (net (code "137") (name "/RSET2") (class "Default")
      (node (ref "R149") (pin "2") (pinfunction "2_2") (pintype "passive"))
      (node (ref "U18") (pin "37") (pinfunction "RSET_37") (pintype "passive"))
    )
    (net (code "138") (name "/RSET3") (class "Default")
      (node (ref "R150") (pin "2") (pinfunction "2_2") (pintype "passive"))
      (node (ref "U19") (pin "37") (pinfunction "RSET_37") (pintype "passive"))
    )
    (net (code "139") (name "/VN6") (class "Default")
      (node (ref "C50") (pin "1") (pinfunction "1_1") (pintype "passive"))
      (node (ref "P17") (pin "3") (pinfunction "3_3") (pintype "passive"))
    )
    (net (code "140") (name "/VREF") (class "Default")
      (node (ref "U15") (pin "2") (pinfunction "IN-_2") (pintype "passive"))
      (node (ref "U15") (pin "6") (pinfunction "OUT_6") (pintype "passive"))
      (node (ref "U17") (pin "36") (pinfunction "VREF_36") (pintype "passive"))
      (node (ref "U18") (pin "36") (pinfunction "VREF_36") (pintype "passive"))
      (node (ref "U19") (pin "36") (pinfunction "VREF_36") (pintype "passive"))
    )
    (net (code "141") (name "/VSSIV") (class "Default")
      (node (ref "P17") (pin "2") (pinfunction "2_2") (pintype "passive"))
      (node (ref "P17") (pin "4") (pinfunction "4_4") (pintype "passive"))
      (node (ref "U10") (pin "4") (pinfunction "V-_4") (pintype "passive"))
      (node (ref "U10") (pin "9") (pinfunction "V-_9") (pintype "passive"))
      (node (ref "U11") (pin "4") (pinfunction "V-_4") (pintype "passive"))
      (node (ref "U11") (pin "9") (pinfunction "V-_9") (pintype "passive"))
      (node (ref "U12") (pin "4") (pinfunction "V-_4") (pintype "passive"))
      (node (ref "U12") (pin "9") (pinfunction "V-_9") (pintype "passive"))
      (node (ref "U13") (pin "4") (pinfunction "V-_4") (pintype "passive"))
      (node (ref "U13") (pin "9") (pinfunction "V-_9") (pintype "passive"))
      (node (ref "U14") (pin "4") (pinfunction "V-_4") (pintype "passive"))
      (node (ref "U14") (pin "9") (pinfunction "V-_9") (pintype "passive"))
      (node (ref "U7") (pin "4") (pinfunction "V-_4") (pintype "passive"))
      (node (ref "U7") (pin "9") (pinfunction "V-_9") (pintype "passive"))
      (node (ref "U8") (pin "4") (pinfunction "V-_4") (pintype "passive"))
      (node (ref "U8") (pin "9") (pinfunction "V-_9") (pintype "passive"))
      (node (ref "U9") (pin "4") (pinfunction "V-_4") (pintype "passive"))
      (node (ref "U9") (pin "9") (pinfunction "V-_9") (pintype "passive"))
    )
    (net (code "142") (name "Net-(U16-V+)") (class "Default")
      (node (ref "R146") (pin "1") (pinfunction "1_1") (pintype "passive"))
      (node (ref "R147") (pin "1") (pinfunction "1_1") (pintype "passive"))
      (node (ref "U16") (pin "1") (pinfunction "V+_1") (pintype "passive"))
    )
    (net (code "143") (name "Net-(U17-B0)") (class "Default")
      (node (ref "R426") (pin "1") (pinfunction "1_1") (pintype "passive"))
      (node (ref "U17") (pin "16") (pinfunction "B0_16") (pintype "passive"))
    )
    (net (code "144") (name "Net-(U17-B1)") (class "Default")
      (node (ref "R428") (pin "1") (pinfunction "1_1") (pintype "passive"))
      (node (ref "U17") (pin "17") (pinfunction "B1_17") (pintype "passive"))
    )
    (net (code "145") (name "Net-(U17-B2)") (class "Default")
      (node (ref "R430") (pin "1") (pinfunction "1_1") (pintype "passive"))
      (node (ref "U17") (pin "18") (pinfunction "B2_18") (pintype "passive"))
    )
    (net (code "146") (name "Net-(U17-B3)") (class "Default")
      (node (ref "R432") (pin "1") (pinfunction "1_1") (pintype "passive"))
      (node (ref "U17") (pin "19") (pinfunction "B3_19") (pintype "passive"))
    )
    (net (code "147") (name "Net-(U17-B4)") (class "Default")
      (node (ref "R434") (pin "1") (pinfunction "1_1") (pintype "passive"))
      (node (ref "U17") (pin "20") (pinfunction "B4_20") (pintype "passive"))
    )
    (net (code "148") (name "Net-(U17-B5)") (class "Default")
      (node (ref "R436") (pin "1") (pinfunction "1_1") (pintype "passive"))
      (node (ref "U17") (pin "21") (pinfunction "B5_21") (pintype "passive"))
    )
    (net (code "149") (name "Net-(U17-B6)") (class "Default")
      (node (ref "R438") (pin "1") (pinfunction "1_1") (pintype "passive"))
      (node (ref "U17") (pin "22") (pinfunction "B6_22") (pintype "passive"))
    )
    (net (code "150") (name "Net-(U17-B7)") (class "Default")
      (node (ref "R440") (pin "1") (pinfunction "1_1") (pintype "passive"))
      (node (ref "U17") (pin "23") (pinfunction "B7_23") (pintype "passive"))
    )
    (net (code "151") (name "Net-(U17-CLOCK)") (class "Default")
      (node (ref "R238") (pin "1") (pinfunction "1_1") (pintype "passive"))
      (node (ref "U17") (pin "24") (pinfunction "CLOCK_24") (pintype "passive"))
    )
    (net (code "152") (name "Net-(U17-G0)") (class "Default")
      (node (ref "R389") (pin "1") (pinfunction "1_1") (pintype "passive"))
      (node (ref "U17") (pin "3") (pinfunction "G0_3") (pintype "passive"))
    )
    (net (code "153") (name "Net-(U17-G1)") (class "Default")
      (node (ref "R395") (pin "1") (pinfunction "1_1") (pintype "passive"))
      (node (ref "U17") (pin "4") (pinfunction "G1_4") (pintype "passive"))
    )
    (net (code "154") (name "Net-(U17-G2)") (class "Default")
      (node (ref "R401") (pin "1") (pinfunction "1_1") (pintype "passive"))
      (node (ref "U17") (pin "5") (pinfunction "G2_5") (pintype "passive"))
    )
    (net (code "155") (name "Net-(U17-G3)") (class "Default")
      (node (ref "R407") (pin "1") (pinfunction "1_1") (pintype "passive"))
      (node (ref "U17") (pin "6") (pinfunction "G3_6") (pintype "passive"))
    )
    (net (code "156") (name "Net-(U17-G4)") (class "Default")
      (node (ref "R413") (pin "1") (pinfunction "1_1") (pintype "passive"))
      (node (ref "U17") (pin "7") (pinfunction "G4_7") (pintype "passive"))
    )
    (net (code "157") (name "Net-(U17-G5)") (class "Default")
      (node (ref "R418") (pin "1") (pinfunction "1_1") (pintype "passive"))
      (node (ref "U17") (pin "8") (pinfunction "G5_8") (pintype "passive"))
    )
    (net (code "158") (name "Net-(U17-G6)") (class "Default")
      (node (ref "R422") (pin "1") (pinfunction "1_1") (pintype "passive"))
      (node (ref "U17") (pin "9") (pinfunction "G6_9") (pintype "passive"))
    )
    (net (code "159") (name "Net-(U17-G7)") (class "Default")
      (node (ref "R424") (pin "1") (pinfunction "1_1") (pintype "passive"))
      (node (ref "U17") (pin "10") (pinfunction "G7_10") (pintype "passive"))
    )
    (net (code "160") (name "Net-(U17-R0)") (class "Default")
      (node (ref "R419") (pin "2") (pinfunction "2_2") (pintype "passive"))
      (node (ref "U17") (pin "41") (pinfunction "R0_41") (pintype "passive"))
    )
    (net (code "161") (name "Net-(U17-R1)") (class "Default")
      (node (ref "R414") (pin "2") (pinfunction "2_2") (pintype "passive"))
      (node (ref "U17") (pin "42") (pinfunction "R1_42") (pintype "passive"))
    )
    (net (code "162") (name "Net-(U17-R2)") (class "Default")
      (node (ref "R408") (pin "2") (pinfunction "2_2") (pintype "passive"))
      (node (ref "U17") (pin "43") (pinfunction "R2_43") (pintype "passive"))
    )
    (net (code "163") (name "Net-(U17-R3)") (class "Default")
      (node (ref "R402") (pin "2") (pinfunction "2_2") (pintype "passive"))
      (node (ref "U17") (pin "44") (pinfunction "R3_44") (pintype "passive"))
    )
    (net (code "164") (name "Net-(U17-R4)") (class "Default")
      (node (ref "R396") (pin "2") (pinfunction "2_2") (pintype "passive"))
      (node (ref "U17") (pin "45") (pinfunction "R4_45") (pintype "passive"))
    )
    (net (code "165") (name "Net-(U17-R5)") (class "Default")
      (node (ref "R390") (pin "2") (pinfunction "2_2") (pintype "passive"))
      (node (ref "U17") (pin "46") (pinfunction "R5_46") (pintype "passive"))
    )
    (net (code "166") (name "Net-(U17-R6)") (class "Default")
      (node (ref "R384") (pin "2") (pinfunction "2_2") (pintype "passive"))
      (node (ref "U17") (pin "47") (pinfunction "R6_47") (pintype "passive"))
    )
    (net (code "167") (name "Net-(U17-R7)") (class "Default")
      (node (ref "R380") (pin "2") (pinfunction "2_2") (pintype "passive"))
      (node (ref "U17") (pin "48") (pinfunction "R7_48") (pintype "passive"))
    )
    (net (code "168") (name "Net-(U18-B0)") (class "Default")
      (node (ref "R425") (pin "1") (pinfunction "1_1") (pintype "passive"))
      (node (ref "U18") (pin "16") (pinfunction "B0_16") (pintype "passive"))
    )
    (net (code "169") (name "Net-(U18-B1)") (class "Default")
      (node (ref "R427") (pin "1") (pinfunction "1_1") (pintype "passive"))
      (node (ref "U18") (pin "17") (pinfunction "B1_17") (pintype "passive"))
    )
    (net (code "170") (name "Net-(U18-B2)") (class "Default")
      (node (ref "R429") (pin "1") (pinfunction "1_1") (pintype "passive"))
      (node (ref "U18") (pin "18") (pinfunction "B2_18") (pintype "passive"))
    )
    (net (code "171") (name "Net-(U18-B3)") (class "Default")
      (node (ref "R431") (pin "1") (pinfunction "1_1") (pintype "passive"))
      (node (ref "U18") (pin "19") (pinfunction "B3_19") (pintype "passive"))
    )
    (net (code "172") (name "Net-(U18-B4)") (class "Default")
      (node (ref "R433") (pin "1") (pinfunction "1_1") (pintype "passive"))
      (node (ref "U18") (pin "20") (pinfunction "B4_20") (pintype "passive"))
    )
    (net (code "173") (name "Net-(U18-B5)") (class "Default")
      (node (ref "R435") (pin "1") (pinfunction "1_1") (pintype "passive"))
      (node (ref "U18") (pin "21") (pinfunction "B5_21") (pintype "passive"))
    )
    (net (code "174") (name "Net-(U18-B6)") (class "Default")
      (node (ref "R437") (pin "1") (pinfunction "1_1") (pintype "passive"))
      (node (ref "U18") (pin "22") (pinfunction "B6_22") (pintype "passive"))
    )
    (net (code "175") (name "Net-(U18-B7)") (class "Default")
      (node (ref "R439") (pin "1") (pinfunction "1_1") (pintype "passive"))
      (node (ref "U18") (pin "23") (pinfunction "B7_23") (pintype "passive"))
    )
    (net (code "176") (name "Net-(U18-CLOCK)") (class "Default")
      (node (ref "R375") (pin "1") (pinfunction "1_1") (pintype "passive"))
      (node (ref "U18") (pin "24") (pinfunction "CLOCK_24") (pintype "passive"))
    )
    (net (code "177") (name "Net-(U18-G0)") (class "Default")
      (node (ref "R385") (pin "1") (pinfunction "1_1") (pintype "passive"))
      (node (ref "U18") (pin "3") (pinfunction "G0_3") (pintype "passive"))
    )
    (net (code "178") (name "Net-(U18-G1)") (class "Default")
      (node (ref "R391") (pin "1") (pinfunction "1_1") (pintype "passive"))
      (node (ref "U18") (pin "4") (pinfunction "G1_4") (pintype "passive"))
    )
    (net (code "179") (name "Net-(U18-G2)") (class "Default")
      (node (ref "R397") (pin "1") (pinfunction "1_1") (pintype "passive"))
      (node (ref "U18") (pin "5") (pinfunction "G2_5") (pintype "passive"))
    )
    (net (code "180") (name "Net-(U18-G3)") (class "Default")
      (node (ref "R403") (pin "1") (pinfunction "1_1") (pintype "passive"))
      (node (ref "U18") (pin "6") (pinfunction "G3_6") (pintype "passive"))
    )
    (net (code "181") (name "Net-(U18-G4)") (class "Default")
      (node (ref "R409") (pin "1") (pinfunction "1_1") (pintype "passive"))
      (node (ref "U18") (pin "7") (pinfunction "G4_7") (pintype "passive"))
    )
    (net (code "182") (name "Net-(U18-G5)") (class "Default")
      (node (ref "R415") (pin "1") (pinfunction "1_1") (pintype "passive"))
      (node (ref "U18") (pin "8") (pinfunction "G5_8") (pintype "passive"))
    )
    (net (code "183") (name "Net-(U18-G6)") (class "Default")
      (node (ref "R420") (pin "1") (pinfunction "1_1") (pintype "passive"))
      (node (ref "U18") (pin "9") (pinfunction "G6_9") (pintype "passive"))
    )
    (net (code "184") (name "Net-(U18-G7)") (class "Default")
      (node (ref "R423") (pin "1") (pinfunction "1_1") (pintype "passive"))
      (node (ref "U18") (pin "10") (pinfunction "G7_10") (pintype "passive"))
    )
    (net (code "185") (name "Net-(U18-R0)") (class "Default")
      (node (ref "R416") (pin "2") (pinfunction "2_2") (pintype "passive"))
      (node (ref "U18") (pin "41") (pinfunction "R0_41") (pintype "passive"))
    )
    (net (code "186") (name "Net-(U18-R1)") (class "Default")
      (node (ref "R410") (pin "2") (pinfunction "2_2") (pintype "passive"))
      (node (ref "U18") (pin "42") (pinfunction "R1_42") (pintype "passive"))
    )
    (net (code "187") (name "Net-(U18-R2)") (class "Default")
      (node (ref "R404") (pin "2") (pinfunction "2_2") (pintype "passive"))
      (node (ref "U18") (pin "43") (pinfunction "R2_43") (pintype "passive"))
    )
    (net (code "188") (name "Net-(U18-R3)") (class "Default")
      (node (ref "R398") (pin "2") (pinfunction "2_2") (pintype "passive"))
      (node (ref "U18") (pin "44") (pinfunction "R3_44") (pintype "passive"))
    )
    (net (code "189") (name "Net-(U18-R4)") (class "Default")
      (node (ref "R392") (pin "2") (pinfunction "2_2") (pintype "passive"))
      (node (ref "U18") (pin "45") (pinfunction "R4_45") (pintype "passive"))
    )
    (net (code "190") (name "Net-(U18-R5)") (class "Default")
      (node (ref "R386") (pin "2") (pinfunction "2_2") (pintype "passive"))
      (node (ref "U18") (pin "46") (pinfunction "R5_46") (pintype "passive"))
    )
    (net (code "191") (name "Net-(U18-R6)") (class "Default")
      (node (ref "R381") (pin "2") (pinfunction "2_2") (pintype "passive"))
      (node (ref "U18") (pin "47") (pinfunction "R6_47") (pintype "passive"))
    )
    (net (code "192") (name "Net-(U18-R7)") (class "Default")
      (node (ref "R378") (pin "2") (pinfunction "2_2") (pintype "passive"))
      (node (ref "U18") (pin "48") (pinfunction "R7_48") (pintype "passive"))
    )
    (net (code "193") (name "Net-(U19-CLOCK)") (class "Default")
      (node (ref "R376") (pin "1") (pinfunction "1_1") (pintype "passive"))
      (node (ref "U19") (pin "24") (pinfunction "CLOCK_24") (pintype "passive"))
    )
    (net (code "194") (name "Net-(U19-G0)") (class "Default")
      (node (ref "R382") (pin "1") (pinfunction "1_1") (pintype "passive"))
      (node (ref "U19") (pin "3") (pinfunction "G0_3") (pintype "passive"))
    )
    (net (code "195") (name "Net-(U19-G1)") (class "Default")
      (node (ref "R387") (pin "1") (pinfunction "1_1") (pintype "passive"))
      (node (ref "U19") (pin "4") (pinfunction "G1_4") (pintype "passive"))
    )
    (net (code "196") (name "Net-(U19-G2)") (class "Default")
      (node (ref "R393") (pin "1") (pinfunction "1_1") (pintype "passive"))
      (node (ref "U19") (pin "5") (pinfunction "G2_5") (pintype "passive"))
    )
    (net (code "197") (name "Net-(U19-G3)") (class "Default")
      (node (ref "R399") (pin "1") (pinfunction "1_1") (pintype "passive"))
      (node (ref "U19") (pin "6") (pinfunction "G3_6") (pintype "passive"))
    )
    (net (code "198") (name "Net-(U19-G4)") (class "Default")
      (node (ref "R405") (pin "1") (pinfunction "1_1") (pintype "passive"))
      (node (ref "U19") (pin "7") (pinfunction "G4_7") (pintype "passive"))
    )
    (net (code "199") (name "Net-(U19-G5)") (class "Default")
      (node (ref "R411") (pin "1") (pinfunction "1_1") (pintype "passive"))
      (node (ref "U19") (pin "8") (pinfunction "G5_8") (pintype "passive"))
    )
    (net (code "200") (name "Net-(U19-G6)") (class "Default")
      (node (ref "R417") (pin "1") (pinfunction "1_1") (pintype "passive"))
      (node (ref "U19") (pin "9") (pinfunction "G6_9") (pintype "passive"))
    )
    (net (code "201") (name "Net-(U19-G7)") (class "Default")
      (node (ref "R421") (pin "1") (pinfunction "1_1") (pintype "passive"))
      (node (ref "U19") (pin "10") (pinfunction "G7_10") (pintype "passive"))
    )
    (net (code "202") (name "Net-(U19-R0)") (class "Default")
      (node (ref "R412") (pin "2") (pinfunction "2_2") (pintype "passive"))
      (node (ref "U19") (pin "41") (pinfunction "R0_41") (pintype "passive"))
    )
    (net (code "203") (name "Net-(U19-R1)") (class "Default")
      (node (ref "R406") (pin "2") (pinfunction "2_2") (pintype "passive"))
      (node (ref "U19") (pin "42") (pinfunction "R1_42") (pintype "passive"))
    )
    (net (code "204") (name "Net-(U19-R2)") (class "Default")
      (node (ref "R400") (pin "2") (pinfunction "2_2") (pintype "passive"))
      (node (ref "U19") (pin "43") (pinfunction "R2_43") (pintype "passive"))
    )
    (net (code "205") (name "Net-(U19-R3)") (class "Default")
      (node (ref "R394") (pin "2") (pinfunction "2_2") (pintype "passive"))
      (node (ref "U19") (pin "44") (pinfunction "R3_44") (pintype "passive"))
    )
    (net (code "206") (name "Net-(U19-R4)") (class "Default")
      (node (ref "R388") (pin "2") (pinfunction "2_2") (pintype "passive"))
      (node (ref "U19") (pin "45") (pinfunction "R4_45") (pintype "passive"))
    )
    (net (code "207") (name "Net-(U19-R5)") (class "Default")
      (node (ref "R383") (pin "2") (pinfunction "2_2") (pintype "passive"))
      (node (ref "U19") (pin "46") (pinfunction "R5_46") (pintype "passive"))
    )
    (net (code "208") (name "Net-(U19-R6)") (class "Default")
      (node (ref "R379") (pin "2") (pinfunction "2_2") (pintype "passive"))
      (node (ref "U19") (pin "47") (pinfunction "R6_47") (pintype "passive"))
    )
    (net (code "209") (name "Net-(U19-R7)") (class "Default")
      (node (ref "R377") (pin "2") (pinfunction "2_2") (pintype "passive"))
      (node (ref "U19") (pin "48") (pinfunction "R7_48") (pintype "passive"))
    )
    (net (code "210") (name "unconnected-(R98-BOT-Pad3)") (class "Default")
      (node (ref "R98") (pin "3") (pinfunction "BOT_3") (pintype "passive+no_connect"))
    )
    (net (code "211") (name "unconnected-(R99-BOT-Pad3)") (class "Default")
      (node (ref "R99") (pin "3") (pinfunction "BOT_3") (pintype "passive+no_connect"))
    )
    (net (code "212") (name "unconnected-(R100-BOT-Pad3)") (class "Default")
      (node (ref "R100") (pin "3") (pinfunction "BOT_3") (pintype "passive+no_connect"))
    )
    (net (code "213") (name "unconnected-(R101-BOT-Pad3)") (class "Default")
      (node (ref "R101") (pin "3") (pinfunction "BOT_3") (pintype "passive+no_connect"))
    )
    (net (code "214") (name "unconnected-(R110-BOT-Pad3)") (class "Default")
      (node (ref "R110") (pin "3") (pinfunction "BOT_3") (pintype "passive+no_connect"))
    )
    (net (code "215") (name "unconnected-(R111-BOT-Pad3)") (class "Default")
      (node (ref "R111") (pin "3") (pinfunction "BOT_3") (pintype "passive+no_connect"))
    )
    (net (code "216") (name "unconnected-(R112-BOT-Pad3)") (class "Default")
      (node (ref "R112") (pin "3") (pinfunction "BOT_3") (pintype "passive+no_connect"))
    )
    (net (code "217") (name "unconnected-(R113-BOT-Pad3)") (class "Default")
      (node (ref "R113") (pin "3") (pinfunction "BOT_3") (pintype "passive+no_connect"))
    )
    (net (code "218") (name "unconnected-(R122-BOT-Pad3)") (class "Default")
      (node (ref "R122") (pin "3") (pinfunction "BOT_3") (pintype "passive+no_connect"))
    )
    (net (code "219") (name "unconnected-(R123-BOT-Pad3)") (class "Default")
      (node (ref "R123") (pin "3") (pinfunction "BOT_3") (pintype "passive+no_connect"))
    )
    (net (code "220") (name "unconnected-(R124-BOT-Pad3)") (class "Default")
      (node (ref "R124") (pin "3") (pinfunction "BOT_3") (pintype "passive+no_connect"))
    )
    (net (code "221") (name "unconnected-(R125-BOT-Pad3)") (class "Default")
      (node (ref "R125") (pin "3") (pinfunction "BOT_3") (pintype "passive+no_connect"))
    )
    (net (code "222") (name "unconnected-(R134-BOT-Pad3)") (class "Default")
      (node (ref "R134") (pin "3") (pinfunction "BOT_3") (pintype "passive+no_connect"))
    )
    (net (code "223") (name "unconnected-(R135-BOT-Pad3)") (class "Default")
      (node (ref "R135") (pin "3") (pinfunction "BOT_3") (pintype "passive+no_connect"))
    )
    (net (code "224") (name "unconnected-(R136-BOT-Pad3)") (class "Default")
      (node (ref "R136") (pin "3") (pinfunction "BOT_3") (pintype "passive+no_connect"))
    )
    (net (code "225") (name "unconnected-(R137-BOT-Pad3)") (class "Default")
      (node (ref "R137") (pin "3") (pinfunction "BOT_3") (pintype "passive+no_connect"))
    )
    (net (code "226") (name "unconnected-(U15-N.C-Pad8)") (class "Default")
      (node (ref "U15") (pin "8") (pinfunction "N.C_8") (pintype "passive+no_connect"))
    )
    (net (code "227") (name "unconnected-(U15-NULL-Pad1)") (class "Default")
      (node (ref "U15") (pin "1") (pinfunction "NULL_1") (pintype "passive+no_connect"))
    )
    (net (code "228") (name "unconnected-(U15-NULL-Pad5)") (class "Default")
      (node (ref "U15") (pin "5") (pinfunction "NULL_5") (pintype "passive+no_connect"))
    )
    (net (code "229") (name "unconnected-(U16-N.C-Pad3)") (class "Default")
      (node (ref "U16") (pin "3") (pinfunction "N.C_3") (pintype "passive+no_connect"))
    )
  )
)
